# SteppyMk2_10x10.net
KiCad netlist of a schematic drawn in EAGLE
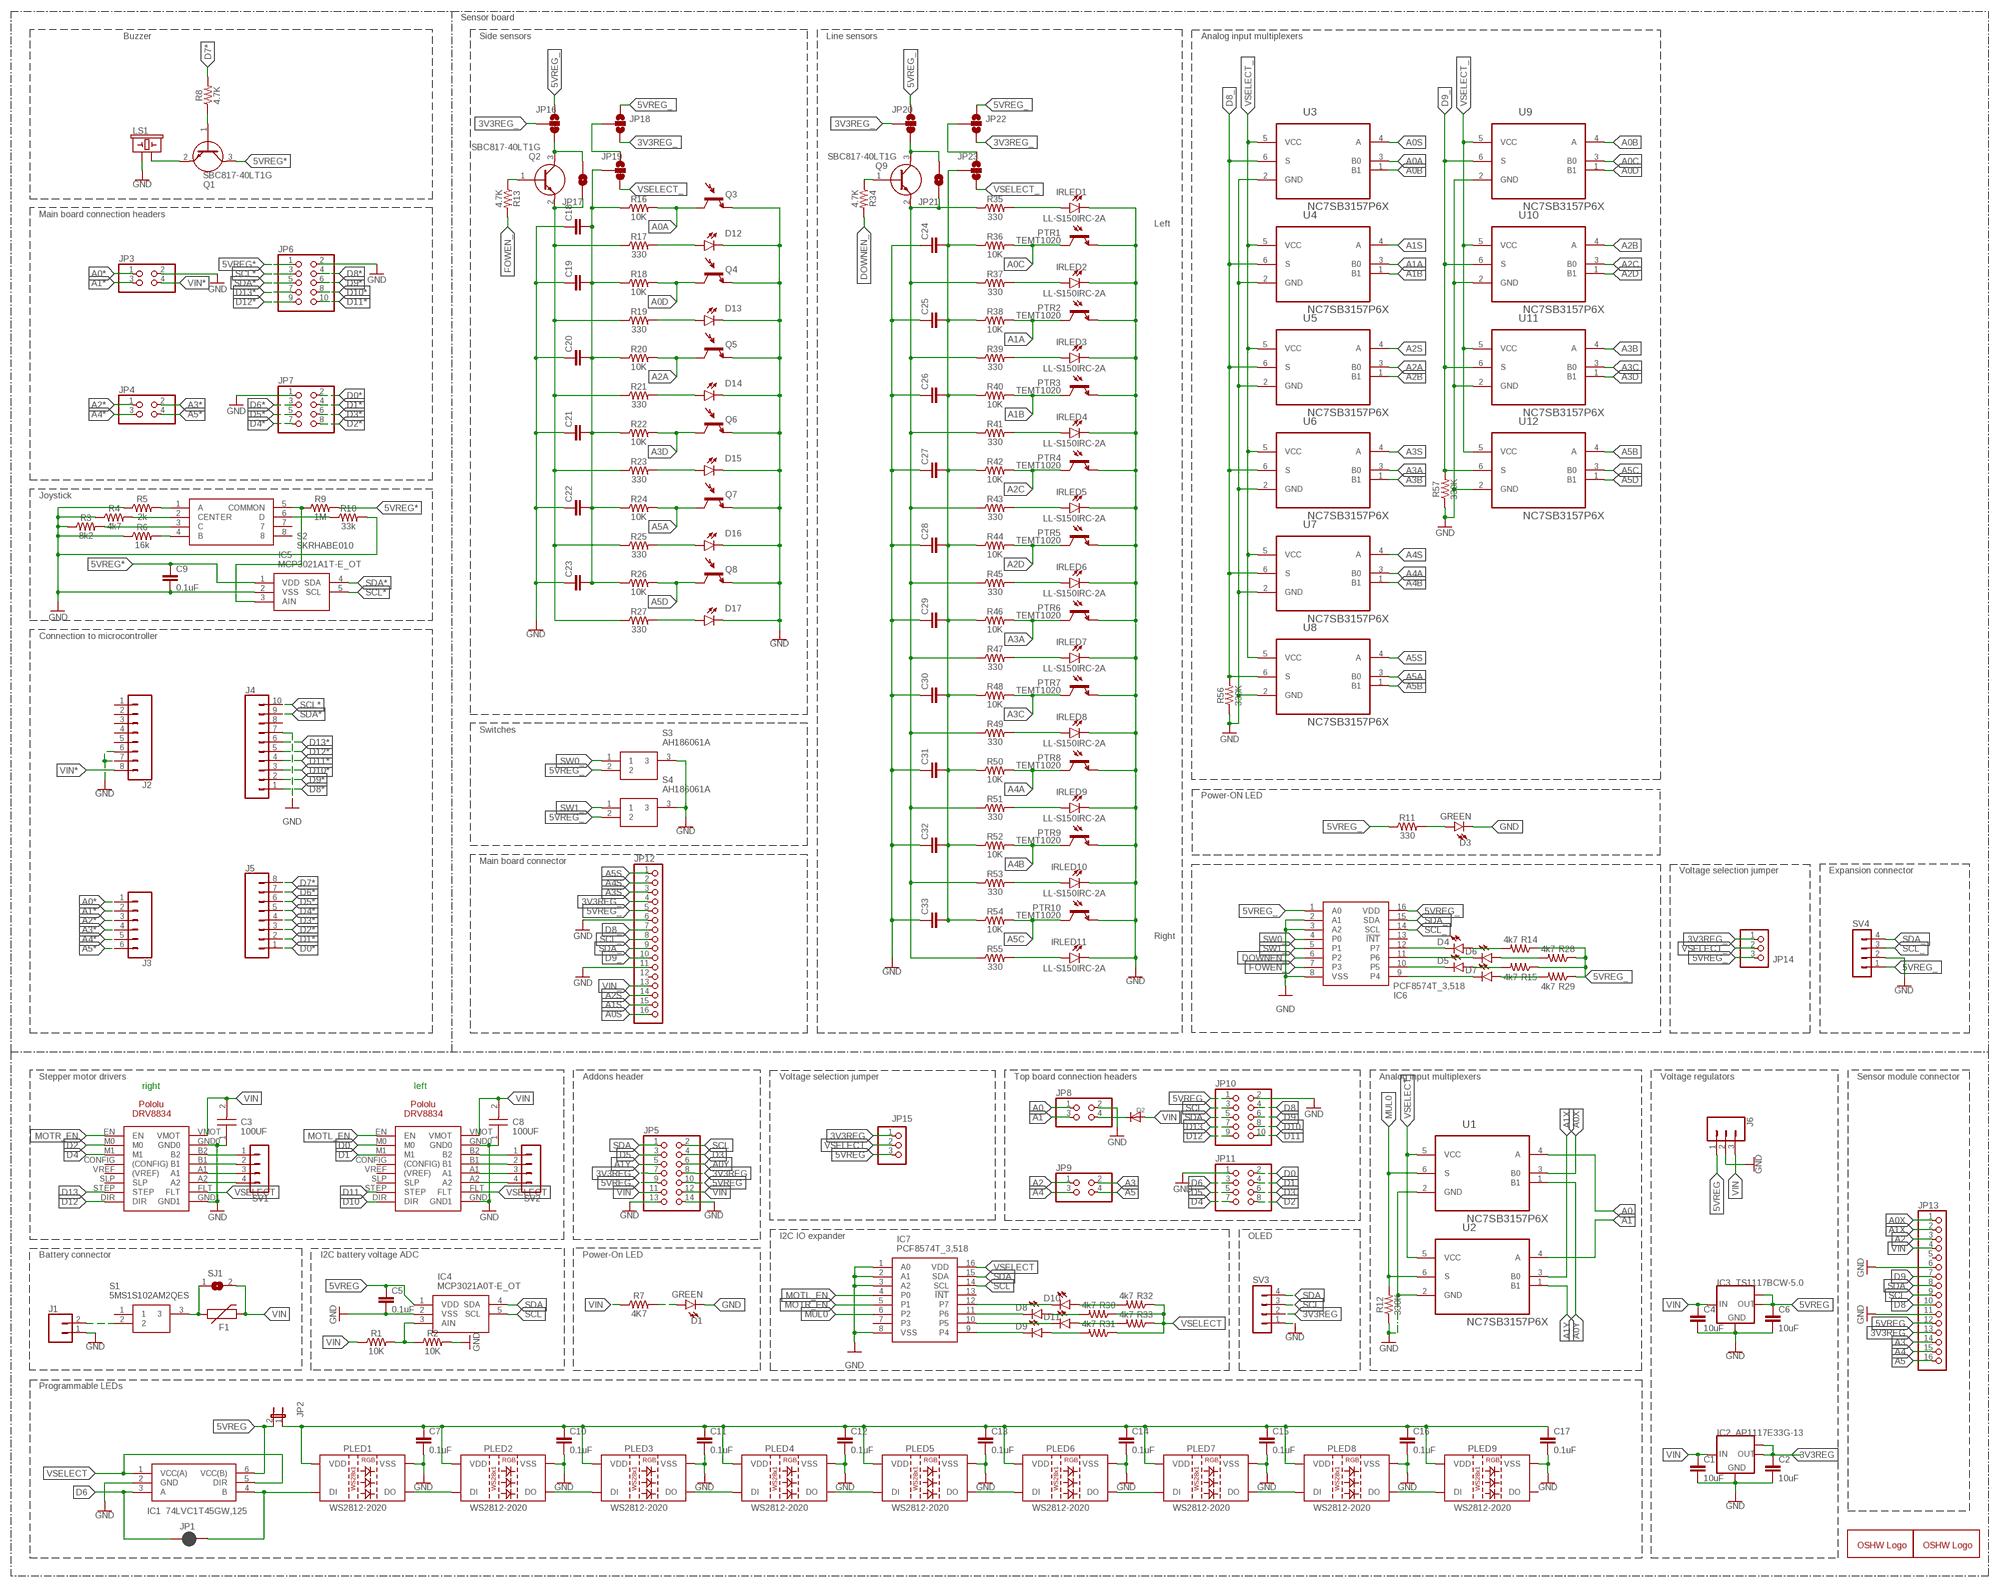
[diagram p0: schematic, sheet 1]

(export (version "E")
  (design (tool "Eeschema 10.0.6"))
  (components
    (comp (ref "C1")
      (value "10uF")
      (footprint "eagle-import:0805")
      (libsource (lib "eagle-import") (part "10UF-0805-10V-10%"))
    )
    (comp (ref "C2")
      (value "10uF")
      (footprint "eagle-import:0805")
      (libsource (lib "eagle-import") (part "10UF-0805-10V-10%"))
    )
    (comp (ref "C3")
      (value "100UF")
      (footprint "eagle-import:CAPM7058X610N")
      (fields
        (field (name "MANUFACTURER_PART_NUMBER") "EEEFK1C101P")
        (field (name "RS_PART_NUMBER") "5370433P")
      )
      (libsource (lib "eagle-import") (part "EEEFK1C101P"))
    )
    (comp (ref "C4")
      (value "10uF")
      (footprint "eagle-import:0805")
      (libsource (lib "eagle-import") (part "10UF-0805-10V-10%"))
    )
    (comp (ref "C5")
      (value "0.1uF")
      (footprint "eagle-import:0603")
      (libsource (lib "eagle-import") (part "0.1UF-0603-25V-5%"))
    )
    (comp (ref "C6")
      (value "10uF")
      (footprint "eagle-import:0805")
      (libsource (lib "eagle-import") (part "10UF-0805-10V-10%"))
    )
    (comp (ref "C7")
      (value "0.1uF")
      (footprint "eagle-import:C0805")
      (libsource (lib "eagle-import") (part "C-EUC0805"))
    )
    (comp (ref "C8")
      (value "100UF")
      (footprint "eagle-import:CAPM7058X610N")
      (fields
        (field (name "MANUFACTURER_PART_NUMBER") "EEEFK1C101P")
        (field (name "RS_PART_NUMBER") "5370433P")
      )
      (libsource (lib "eagle-import") (part "EEEFK1C101P"))
    )
    (comp (ref "C9")
      (value "0.1uF")
      (footprint "eagle-import:C0805")
      (libsource (lib "eagle-import") (part "C-EUC0805"))
    )
    (comp (ref "C10")
      (value "0.1uF")
      (footprint "eagle-import:C0805")
      (libsource (lib "eagle-import") (part "C-EUC0805"))
    )
    (comp (ref "C11")
      (value "0.1uF")
      (footprint "eagle-import:C0805")
      (libsource (lib "eagle-import") (part "C-EUC0805"))
    )
    (comp (ref "C12")
      (value "0.1uF")
      (footprint "eagle-import:C0805")
      (libsource (lib "eagle-import") (part "C-EUC0805"))
    )
    (comp (ref "C13")
      (value "0.1uF")
      (footprint "eagle-import:C0805")
      (libsource (lib "eagle-import") (part "C-EUC0805"))
    )
    (comp (ref "C14")
      (value "0.1uF")
      (footprint "eagle-import:C0805")
      (libsource (lib "eagle-import") (part "C-EUC0805"))
    )
    (comp (ref "C15")
      (value "0.1uF")
      (footprint "eagle-import:C0805")
      (libsource (lib "eagle-import") (part "C-EUC0805"))
    )
    (comp (ref "C16")
      (value "0.1uF")
      (footprint "eagle-import:C0805")
      (libsource (lib "eagle-import") (part "C-EUC0805"))
    )
    (comp (ref "C17")
      (value "0.1uF")
      (footprint "eagle-import:C0805")
      (libsource (lib "eagle-import") (part "C-EUC0805"))
    )
    (comp (ref "C18")
      (value "C-EUC0805")
      (footprint "eagle-import:C0805")
      (libsource (lib "eagle-import") (part "C-EUC0805"))
    )
    (comp (ref "C19")
      (value "C-EUC0805")
      (footprint "eagle-import:C0805")
      (libsource (lib "eagle-import") (part "C-EUC0805"))
    )
    (comp (ref "C20")
      (value "C-EUC0805")
      (footprint "eagle-import:C0805")
      (libsource (lib "eagle-import") (part "C-EUC0805"))
    )
    (comp (ref "C21")
      (value "C-EUC0805")
      (footprint "eagle-import:C0805")
      (libsource (lib "eagle-import") (part "C-EUC0805"))
    )
    (comp (ref "C22")
      (value "C-EUC0805")
      (footprint "eagle-import:C0805")
      (libsource (lib "eagle-import") (part "C-EUC0805"))
    )
    (comp (ref "C23")
      (value "C-EUC0805")
      (footprint "eagle-import:C0805")
      (libsource (lib "eagle-import") (part "C-EUC0805"))
    )
    (comp (ref "C24")
      (value "C-EUC0805")
      (footprint "eagle-import:C0805")
      (libsource (lib "eagle-import") (part "C-EUC0805"))
    )
    (comp (ref "C25")
      (value "C-EUC0805")
      (footprint "eagle-import:C0805")
      (libsource (lib "eagle-import") (part "C-EUC0805"))
    )
    (comp (ref "C26")
      (value "C-EUC0805")
      (footprint "eagle-import:C0805")
      (libsource (lib "eagle-import") (part "C-EUC0805"))
    )
    (comp (ref "C27")
      (value "C-EUC0805")
      (footprint "eagle-import:C0805")
      (libsource (lib "eagle-import") (part "C-EUC0805"))
    )
    (comp (ref "C28")
      (value "C-EUC0805")
      (footprint "eagle-import:C0805")
      (libsource (lib "eagle-import") (part "C-EUC0805"))
    )
    (comp (ref "C29")
      (value "C-EUC0805")
      (footprint "eagle-import:C0805")
      (libsource (lib "eagle-import") (part "C-EUC0805"))
    )
    (comp (ref "C30")
      (value "C-EUC0805")
      (footprint "eagle-import:C0805")
      (libsource (lib "eagle-import") (part "C-EUC0805"))
    )
    (comp (ref "C31")
      (value "C-EUC0805")
      (footprint "eagle-import:C0805")
      (libsource (lib "eagle-import") (part "C-EUC0805"))
    )
    (comp (ref "C32")
      (value "C-EUC0805")
      (footprint "eagle-import:C0805")
      (libsource (lib "eagle-import") (part "C-EUC0805"))
    )
    (comp (ref "C33")
      (value "C-EUC0805")
      (footprint "eagle-import:C0805")
      (libsource (lib "eagle-import") (part "C-EUC0805"))
    )
    (comp (ref "D1")
      (value "GREEN")
      (footprint "eagle-import:LED-1206")
      (libsource (lib "eagle-import") (part "LED-GREEN1206"))
    )
    (comp (ref "D2")
      (value "DIODESMA")
      (footprint "eagle-import:SMADIODE")
      (libsource (lib "eagle-import") (part "DIODESMA"))
    )
    (comp (ref "D3")
      (value "GREEN")
      (footprint "eagle-import:LED-1206")
      (libsource (lib "eagle-import") (part "LED-GREEN1206"))
    )
    (comp (ref "D4")
      (value "GREEN")
      (footprint "eagle-import:LED-1206")
      (libsource (lib "eagle-import") (part "LED-GREEN1206"))
    )
    (comp (ref "D5")
      (value "GREEN")
      (footprint "eagle-import:LED-1206")
      (libsource (lib "eagle-import") (part "LED-GREEN1206"))
    )
    (comp (ref "D6")
      (value "GREEN")
      (footprint "eagle-import:LED-1206")
      (libsource (lib "eagle-import") (part "LED-GREEN1206"))
    )
    (comp (ref "D7")
      (value "GREEN")
      (footprint "eagle-import:LED-1206")
      (libsource (lib "eagle-import") (part "LED-GREEN1206"))
    )
    (comp (ref "D8")
      (value "GREEN")
      (footprint "eagle-import:LED-1206")
      (libsource (lib "eagle-import") (part "LED-GREEN1206"))
    )
    (comp (ref "D9")
      (value "GREEN")
      (footprint "eagle-import:LED-1206")
      (libsource (lib "eagle-import") (part "LED-GREEN1206"))
    )
    (comp (ref "D10")
      (value "GREEN")
      (footprint "eagle-import:LED-1206")
      (libsource (lib "eagle-import") (part "LED-GREEN1206"))
    )
    (comp (ref "D11")
      (value "GREEN")
      (footprint "eagle-import:LED-1206")
      (libsource (lib "eagle-import") (part "LED-GREEN1206"))
    )
    (comp (ref "D12")
      (value "LED-IRSIDE_EMITTER")
      (footprint "eagle-import:LTE-302")
      (libsource (lib "eagle-import") (part "LED-IRSIDE_EMITTER"))
    )
    (comp (ref "D13")
      (value "LED-IRSIDE_EMITTER")
      (footprint "eagle-import:LTE-302")
      (libsource (lib "eagle-import") (part "LED-IRSIDE_EMITTER"))
    )
    (comp (ref "D14")
      (value "LED-IRSIDE_EMITTER")
      (footprint "eagle-import:LTE-302")
      (libsource (lib "eagle-import") (part "LED-IRSIDE_EMITTER"))
    )
    (comp (ref "D15")
      (value "LED-IRSIDE_EMITTER")
      (footprint "eagle-import:LTE-302")
      (libsource (lib "eagle-import") (part "LED-IRSIDE_EMITTER"))
    )
    (comp (ref "D16")
      (value "LED-IRSIDE_EMITTER")
      (footprint "eagle-import:LTE-302")
      (libsource (lib "eagle-import") (part "LED-IRSIDE_EMITTER"))
    )
    (comp (ref "D17")
      (value "LED-IRSIDE_EMITTER")
      (footprint "eagle-import:LTE-302")
      (libsource (lib "eagle-import") (part "LED-IRSIDE_EMITTER"))
    )
    (comp (ref "DRV1")
      (value "POLOLU-DRV8825")
      (footprint "eagle-import:POLOLU-DRV8825")
      (libsource (lib "eagle-import") (part "POLOLU-DRV8825"))
    )
    (comp (ref "DRV2")
      (value "POLOLU-DRV8825")
      (footprint "eagle-import:POLOLU-DRV8825")
      (libsource (lib "eagle-import") (part "POLOLU-DRV8825"))
    )
    (comp (ref "F1")
      (value "PPTC_PTH")
      (footprint "eagle-import:PTH")
      (libsource (lib "eagle-import") (part "PPTC_PTH"))
    )
    (comp (ref "GOLD_ORB_SM1")
      (value "OSHWLOGOLOGO8MM")
      (footprint "eagle-import:OSHW_8MM")
      (libsource (lib "eagle-import") (part "OSHWLOGOLOGO8MM"))
    )
    (comp (ref "GOLD_ORB_SM2")
      (value "OSHWLOGOLOGO5MM")
      (footprint "eagle-import:OSHW_5MM")
      (libsource (lib "eagle-import") (part "OSHWLOGOLOGO5MM"))
    )
    (comp (ref "IC1")
      (value "74LVC1T45GW,125")
      (footprint "eagle-import:SOT65P210X110-6N")
      (fields
        (field (name "MOUSER_PART_NUMBER") "771-74LVC1T45GW125")
        (field (name "RS_PART_NUMBER") "8168791P")
      )
      (libsource (lib "eagle-import") (part "74LVC1T45GW,125"))
    )
    (comp (ref "IC2")
      (value "AP1117E33G-13")
      (footprint "eagle-import:SOT223")
      (libsource (lib "eagle-import") (part "LM1117IMPX-3.3"))
    )
    (comp (ref "IC3")
      (value "TS1117BCW-5.0")
      (footprint "eagle-import:SOT223")
      (libsource (lib "eagle-import") (part "LM1117IMPX-5.0"))
    )
    (comp (ref "IC4")
      (value "MCP3021A0T-E_OT")
      (footprint "eagle-import:SOT95P280X145-5N")
      (fields
        (field (name "MANUFACTURER_PART_NUMBER") "MCP3021A0T-E/OT")
        (field (name "MOUSER_PART_NUMBER") "579-MCP3021A0T-E/OT")
      )
      (libsource (lib "eagle-import") (part "MCP3021A0T-E_OT"))
    )
    (comp (ref "IC5")
      (value "MCP3021A1T-E_OT")
      (footprint "eagle-import:SOT95P280X145-5N")
      (fields
        (field (name "MANUFACTURER_PART_NUMBER") "MCP3021A0T-E/OT")
        (field (name "MOUSER_PART_NUMBER") "579-MCP3021A0T-E/OT")
      )
      (libsource (lib "eagle-import") (part "MCP3021A0T-E_OT"))
    )
    (comp (ref "IC6")
      (value "PCF8574T_3,518")
      (footprint "eagle-import:SOIC127P1032X265-16N")
      (fields
        (field (name "MANUFACTURER_PART_NUMBER") "PCF8574T/3,518")
        (field (name "MOUSER_PART_NUMBER") "771-PCF8574TD-T")
      )
      (libsource (lib "eagle-import") (part "PCF8574T_3,518"))
    )
    (comp (ref "IC7")
      (value "PCF8574T_3,518")
      (footprint "eagle-import:SOIC127P1032X265-16N")
      (fields
        (field (name "MANUFACTURER_PART_NUMBER") "PCF8574T/3,518")
        (field (name "MOUSER_PART_NUMBER") "771-PCF8574TD-T")
      )
      (libsource (lib "eagle-import") (part "PCF8574T_3,518"))
    )
    (comp (ref "IRLED1")
      (value "LL-S150IRC-2A")
      (footprint "eagle-import:LEDC3215X130N")
      (fields
        (field (name "MANUFACTURER_PART_NUMBER") "PT15-21C/TR8")
        (field (name "MOUSER_PART_NUMBER") "638-PT1521CTR8")
      )
      (libsource (lib "eagle-import") (part "PT15-21C_TR8"))
    )
    (comp (ref "IRLED2")
      (value "LL-S150IRC-2A")
      (footprint "eagle-import:LEDC3215X130N")
      (fields
        (field (name "MANUFACTURER_PART_NUMBER") "PT15-21C/TR8")
        (field (name "MOUSER_PART_NUMBER") "638-PT1521CTR8")
      )
      (libsource (lib "eagle-import") (part "PT15-21C_TR8"))
    )
    (comp (ref "IRLED3")
      (value "LL-S150IRC-2A")
      (footprint "eagle-import:LEDC3215X130N")
      (fields
        (field (name "MANUFACTURER_PART_NUMBER") "PT15-21C/TR8")
        (field (name "MOUSER_PART_NUMBER") "638-PT1521CTR8")
      )
      (libsource (lib "eagle-import") (part "PT15-21C_TR8"))
    )
    (comp (ref "IRLED4")
      (value "LL-S150IRC-2A")
      (footprint "eagle-import:LEDC3215X130N")
      (fields
        (field (name "MANUFACTURER_PART_NUMBER") "PT15-21C/TR8")
        (field (name "MOUSER_PART_NUMBER") "638-PT1521CTR8")
      )
      (libsource (lib "eagle-import") (part "PT15-21C_TR8"))
    )
    (comp (ref "IRLED5")
      (value "LL-S150IRC-2A")
      (footprint "eagle-import:LEDC3215X130N")
      (fields
        (field (name "MANUFACTURER_PART_NUMBER") "PT15-21C/TR8")
        (field (name "MOUSER_PART_NUMBER") "638-PT1521CTR8")
      )
      (libsource (lib "eagle-import") (part "PT15-21C_TR8"))
    )
    (comp (ref "IRLED6")
      (value "LL-S150IRC-2A")
      (footprint "eagle-import:LEDC3215X130N")
      (fields
        (field (name "MANUFACTURER_PART_NUMBER") "PT15-21C/TR8")
        (field (name "MOUSER_PART_NUMBER") "638-PT1521CTR8")
      )
      (libsource (lib "eagle-import") (part "PT15-21C_TR8"))
    )
    (comp (ref "IRLED7")
      (value "LL-S150IRC-2A")
      (footprint "eagle-import:LEDC3215X130N")
      (fields
        (field (name "MANUFACTURER_PART_NUMBER") "PT15-21C/TR8")
        (field (name "MOUSER_PART_NUMBER") "638-PT1521CTR8")
      )
      (libsource (lib "eagle-import") (part "PT15-21C_TR8"))
    )
    (comp (ref "IRLED8")
      (value "LL-S150IRC-2A")
      (footprint "eagle-import:LEDC3215X130N")
      (fields
        (field (name "MANUFACTURER_PART_NUMBER") "PT15-21C/TR8")
        (field (name "MOUSER_PART_NUMBER") "638-PT1521CTR8")
      )
      (libsource (lib "eagle-import") (part "PT15-21C_TR8"))
    )
    (comp (ref "IRLED9")
      (value "LL-S150IRC-2A")
      (footprint "eagle-import:LEDC3215X130N")
      (fields
        (field (name "MANUFACTURER_PART_NUMBER") "PT15-21C/TR8")
        (field (name "MOUSER_PART_NUMBER") "638-PT1521CTR8")
      )
      (libsource (lib "eagle-import") (part "PT15-21C_TR8"))
    )
    (comp (ref "IRLED10")
      (value "LL-S150IRC-2A")
      (footprint "eagle-import:LEDC3215X130N")
      (fields
        (field (name "MANUFACTURER_PART_NUMBER") "PT15-21C/TR8")
        (field (name "MOUSER_PART_NUMBER") "638-PT1521CTR8")
      )
      (libsource (lib "eagle-import") (part "PT15-21C_TR8"))
    )
    (comp (ref "IRLED11")
      (value "LL-S150IRC-2A")
      (footprint "eagle-import:LEDC3215X130N")
      (fields
        (field (name "MANUFACTURER_PART_NUMBER") "PT15-21C/TR8")
        (field (name "MOUSER_PART_NUMBER") "638-PT1521CTR8")
      )
      (libsource (lib "eagle-import") (part "PT15-21C_TR8"))
    )
    (comp (ref "J1")
      (value "CONN_02")
      (footprint "eagle-import:1X02")
      (libsource (lib "eagle-import") (part "CONN_02"))
    )
    (comp (ref "J2")
      (value "CONN_08\"")
      (footprint "eagle-import:1X08")
      (libsource (lib "eagle-import") (part "CONN_08{dblquote}"))
    )
    (comp (ref "J3")
      (value "CONN_06SILK_FEMALE_PTH")
      (footprint "eagle-import:1X06")
      (libsource (lib "eagle-import") (part "CONN_06SILK_FEMALE_PTH"))
    )
    (comp (ref "J4")
      (value "CONN_10\"")
      (footprint "eagle-import:1X10")
      (libsource (lib "eagle-import") (part "CONN_10{dblquote}"))
    )
    (comp (ref "J5")
      (value "CONN_08\"")
      (footprint "eagle-import:1X08")
      (libsource (lib "eagle-import") (part "CONN_08{dblquote}"))
    )
    (comp (ref "J6")
      (value "455-1750-1-ND")
      (footprint "eagle-import:1X03")
      (libsource (lib "eagle-import") (part "CONN_03"))
    )
    (comp (ref "JP1")
      (value "JUMPER-SMT_2_NC_PASTE_SILK")
      (footprint "eagle-import:SMT-JUMPER_2_NC_PASTE_SILK")
      (libsource (lib "eagle-import") (part "JUMPER-SMT_2_NC_PASTE_SILK"))
    )
    (comp (ref "JP2")
      (value "JP1E")
      (footprint "eagle-import:JP1")
      (libsource (lib "eagle-import") (part "JP1E"))
    )
    (comp (ref "JP3")
      (value "PINHD-2X2")
      (footprint "eagle-import:2X02")
      (libsource (lib "eagle-import") (part "PINHD-2X2"))
    )
    (comp (ref "JP4")
      (value "PINHD-2X2")
      (footprint "eagle-import:2X02")
      (libsource (lib "eagle-import") (part "PINHD-2X2"))
    )
    (comp (ref "JP5")
      (value "PINHD-2X7")
      (footprint "eagle-import:2X07")
      (libsource (lib "eagle-import") (part "PINHD-2X7"))
    )
    (comp (ref "JP6")
      (value "PINHD-2X5")
      (footprint "eagle-import:2X05")
      (libsource (lib "eagle-import") (part "PINHD-2X5"))
    )
    (comp (ref "JP7")
      (value "PINHD-2X4")
      (footprint "eagle-import:2X04")
      (libsource (lib "eagle-import") (part "PINHD-2X4"))
    )
    (comp (ref "JP8")
      (value "PINHD-2X2")
      (footprint "eagle-import:2X02")
      (libsource (lib "eagle-import") (part "PINHD-2X2"))
    )
    (comp (ref "JP9")
      (value "PINHD-2X2")
      (footprint "eagle-import:2X02")
      (libsource (lib "eagle-import") (part "PINHD-2X2"))
    )
    (comp (ref "JP10")
      (value "PINHD-2X5")
      (footprint "eagle-import:2X05")
      (libsource (lib "eagle-import") (part "PINHD-2X5"))
    )
    (comp (ref "JP11")
      (value "PINHD-2X4")
      (footprint "eagle-import:2X04")
      (libsource (lib "eagle-import") (part "PINHD-2X4"))
    )
    (comp (ref "JP12")
      (value "PINHD-1X16/90")
      (footprint "eagle-import:1X16_90")
      (libsource (lib "eagle-import") (part "PINHD-1X16/90"))
    )
    (comp (ref "JP13")
      (value "PINHD-1X16")
      (footprint "eagle-import:1X16")
      (libsource (lib "eagle-import") (part "PINHD-1X16"))
    )
    (comp (ref "JP14")
      (value "PINHD-1X3")
      (footprint "eagle-import:1X03")
      (libsource (lib "eagle-import") (part "PINHD-1X3"))
    )
    (comp (ref "JP15")
      (value "PINHD-1X3")
      (footprint "eagle-import:1X03")
      (libsource (lib "eagle-import") (part "PINHD-1X3"))
    )
    (comp (ref "JP16")
      (value "JUMPER-SMT_3_1-NC_TRACE_NO-SILK")
      (footprint "eagle-import:SMT-JUMPER_3_1-NC_TRACE_NO-SILK")
      (libsource (lib "eagle-import") (part "JUMPER-SMT_3_1-NC_TRACE_NO-SILK"))
    )
    (comp (ref "JP17")
      (value "JUMPER-SMT_2_NO_NO-SILK")
      (footprint "eagle-import:SMT-JUMPER_2_NO_NO-SILK")
      (libsource (lib "eagle-import") (part "JUMPER-SMT_2_NO_NO-SILK"))
    )
    (comp (ref "JP18")
      (value "JUMPER-SMT_3_NO_NO_SILK")
      (footprint "eagle-import:SMT-JUMPER_3_0-NO_TRACE_NO-SILK")
      (libsource (lib "eagle-import") (part "JUMPER-SMT_3_NO_NO_SILK"))
    )
    (comp (ref "JP19")
      (value "JUMPER-SMT_3_1-NC_TRACE_NO-SILK")
      (footprint "eagle-import:SMT-JUMPER_3_1-NC_TRACE_NO-SILK")
      (libsource (lib "eagle-import") (part "JUMPER-SMT_3_1-NC_TRACE_NO-SILK"))
    )
    (comp (ref "JP20")
      (value "JUMPER-SMT_3_1-NC_TRACE_NO-SILK")
      (footprint "eagle-import:SMT-JUMPER_3_1-NC_TRACE_NO-SILK")
      (libsource (lib "eagle-import") (part "JUMPER-SMT_3_1-NC_TRACE_NO-SILK"))
    )
    (comp (ref "JP21")
      (value "JUMPER-SMT_2_NO_NO-SILK")
      (footprint "eagle-import:SMT-JUMPER_2_NO_NO-SILK")
      (libsource (lib "eagle-import") (part "JUMPER-SMT_2_NO_NO-SILK"))
    )
    (comp (ref "JP22")
      (value "JUMPER-SMT_3_NO_NO_SILK")
      (footprint "eagle-import:SMT-JUMPER_3_0-NO_TRACE_NO-SILK")
      (libsource (lib "eagle-import") (part "JUMPER-SMT_3_NO_NO_SILK"))
    )
    (comp (ref "JP23")
      (value "JUMPER-SMT_3_1-NC_TRACE_NO-SILK")
      (footprint "eagle-import:SMT-JUMPER_3_1-NC_TRACE_NO-SILK")
      (libsource (lib "eagle-import") (part "JUMPER-SMT_3_1-NC_TRACE_NO-SILK"))
    )
    (comp (ref "LS1")
      (value "BUZZER-PTH_NO_SILK")
      (footprint "eagle-import:BUZZER-12MM-NS")
      (libsource (lib "eagle-import") (part "BUZZER-PTH_NO_SILK"))
    )
    (comp (ref "PLED1")
      (value "WS2812-2020")
      (footprint "eagle-import:WS2812-2020")
      (libsource (lib "eagle-import") (part "WS2812-2020"))
    )
    (comp (ref "PLED2")
      (value "WS2812-2020")
      (footprint "eagle-import:WS2812-2020")
      (libsource (lib "eagle-import") (part "WS2812-2020"))
    )
    (comp (ref "PLED3")
      (value "WS2812-2020")
      (footprint "eagle-import:WS2812-2020")
      (libsource (lib "eagle-import") (part "WS2812-2020"))
    )
    (comp (ref "PLED4")
      (value "WS2812-2020")
      (footprint "eagle-import:WS2812-2020")
      (libsource (lib "eagle-import") (part "WS2812-2020"))
    )
    (comp (ref "PLED5")
      (value "WS2812-2020")
      (footprint "eagle-import:WS2812-2020")
      (libsource (lib "eagle-import") (part "WS2812-2020"))
    )
    (comp (ref "PLED6")
      (value "WS2812-2020")
      (footprint "eagle-import:WS2812-2020")
      (libsource (lib "eagle-import") (part "WS2812-2020"))
    )
    (comp (ref "PLED7")
      (value "WS2812-2020")
      (footprint "eagle-import:WS2812-2020")
      (libsource (lib "eagle-import") (part "WS2812-2020"))
    )
    (comp (ref "PLED8")
      (value "WS2812-2020")
      (footprint "eagle-import:WS2812-2020")
      (libsource (lib "eagle-import") (part "WS2812-2020"))
    )
    (comp (ref "PLED9")
      (value "WS2812-2020")
      (footprint "eagle-import:WS2812-2020")
      (libsource (lib "eagle-import") (part "WS2812-2020"))
    )
    (comp (ref "PTR1")
      (value "TEMT1020")
      (footprint "eagle-import:TEMT1020")
      (fields
        (field (name "MANUFACTURER_PART_NUMBER") "TEMD1020")
        (field (name "MOUSER_PART_NUMBER") "782-TEMD1020")
        (field (name "RS_PART_NUMBER") "1808105P")
      )
      (libsource (lib "eagle-import") (part "TEMT1020"))
    )
    (comp (ref "PTR2")
      (value "TEMT1020")
      (footprint "eagle-import:TEMT1020")
      (fields
        (field (name "MANUFACTURER_PART_NUMBER") "TEMD1020")
        (field (name "MOUSER_PART_NUMBER") "782-TEMD1020")
        (field (name "RS_PART_NUMBER") "1808105P")
      )
      (libsource (lib "eagle-import") (part "TEMT1020"))
    )
    (comp (ref "PTR3")
      (value "TEMT1020")
      (footprint "eagle-import:TEMT1020")
      (fields
        (field (name "MANUFACTURER_PART_NUMBER") "TEMD1020")
        (field (name "MOUSER_PART_NUMBER") "782-TEMD1020")
        (field (name "RS_PART_NUMBER") "1808105P")
      )
      (libsource (lib "eagle-import") (part "TEMT1020"))
    )
    (comp (ref "PTR4")
      (value "TEMT1020")
      (footprint "eagle-import:TEMT1020")
      (fields
        (field (name "MANUFACTURER_PART_NUMBER") "TEMD1020")
        (field (name "MOUSER_PART_NUMBER") "782-TEMD1020")
        (field (name "RS_PART_NUMBER") "1808105P")
      )
      (libsource (lib "eagle-import") (part "TEMT1020"))
    )
    (comp (ref "PTR5")
      (value "TEMT1020")
      (footprint "eagle-import:TEMT1020")
      (fields
        (field (name "MANUFACTURER_PART_NUMBER") "TEMD1020")
        (field (name "MOUSER_PART_NUMBER") "782-TEMD1020")
        (field (name "RS_PART_NUMBER") "1808105P")
      )
      (libsource (lib "eagle-import") (part "TEMT1020"))
    )
    (comp (ref "PTR6")
      (value "TEMT1020")
      (footprint "eagle-import:TEMT1020")
      (fields
        (field (name "MANUFACTURER_PART_NUMBER") "TEMD1020")
        (field (name "MOUSER_PART_NUMBER") "782-TEMD1020")
        (field (name "RS_PART_NUMBER") "1808105P")
      )
      (libsource (lib "eagle-import") (part "TEMT1020"))
    )
    (comp (ref "PTR7")
      (value "TEMT1020")
      (footprint "eagle-import:TEMT1020")
      (fields
        (field (name "MANUFACTURER_PART_NUMBER") "TEMD1020")
        (field (name "MOUSER_PART_NUMBER") "782-TEMD1020")
        (field (name "RS_PART_NUMBER") "1808105P")
      )
      (libsource (lib "eagle-import") (part "TEMT1020"))
    )
    (comp (ref "PTR8")
      (value "TEMT1020")
      (footprint "eagle-import:TEMT1020")
      (fields
        (field (name "MANUFACTURER_PART_NUMBER") "TEMD1020")
        (field (name "MOUSER_PART_NUMBER") "782-TEMD1020")
        (field (name "RS_PART_NUMBER") "1808105P")
      )
      (libsource (lib "eagle-import") (part "TEMT1020"))
    )
    (comp (ref "PTR9")
      (value "TEMT1020")
      (footprint "eagle-import:TEMT1020")
      (fields
        (field (name "MANUFACTURER_PART_NUMBER") "TEMD1020")
        (field (name "MOUSER_PART_NUMBER") "782-TEMD1020")
        (field (name "RS_PART_NUMBER") "1808105P")
      )
      (libsource (lib "eagle-import") (part "TEMT1020"))
    )
    (comp (ref "PTR10")
      (value "TEMT1020")
      (footprint "eagle-import:TEMT1020")
      (fields
        (field (name "MANUFACTURER_PART_NUMBER") "TEMD1020")
        (field (name "MOUSER_PART_NUMBER") "782-TEMD1020")
        (field (name "RS_PART_NUMBER") "1808105P")
      )
      (libsource (lib "eagle-import") (part "TEMT1020"))
    )
    (comp (ref "Q1")
      (value "SBC817-40LT1G")
      (footprint "eagle-import:SOT96P237X111-3N")
      (fields
        (field (name "MOUSER_PART_NUMBER") "863-SBC817-40LT1G")
        (field (name "RS_PART_NUMBER") "1631159")
      )
      (libsource (lib "eagle-import") (part "SBC817-40LT1G"))
    )
    (comp (ref "Q2")
      (value "SBC817-40LT1G")
      (footprint "eagle-import:SOT96P237X111-3N")
      (fields
        (field (name "MOUSER_PART_NUMBER") "863-SBC817-40LT1G")
        (field (name "RS_PART_NUMBER") "1631159")
      )
      (libsource (lib "eagle-import") (part "SBC817-40LT1G"))
    )
    (comp (ref "Q3")
      (value "LTR-301")
      (footprint "eagle-import:LTR-301")
      (libsource (lib "eagle-import") (part "LTR-301"))
    )
    (comp (ref "Q4")
      (value "LTR-301")
      (footprint "eagle-import:LTR-301")
      (libsource (lib "eagle-import") (part "LTR-301"))
    )
    (comp (ref "Q5")
      (value "LTR-301")
      (footprint "eagle-import:LTR-301")
      (libsource (lib "eagle-import") (part "LTR-301"))
    )
    (comp (ref "Q6")
      (value "LTR-301")
      (footprint "eagle-import:LTR-301")
      (libsource (lib "eagle-import") (part "LTR-301"))
    )
    (comp (ref "Q7")
      (value "LTR-301")
      (footprint "eagle-import:LTR-301")
      (libsource (lib "eagle-import") (part "LTR-301"))
    )
    (comp (ref "Q8")
      (value "LTR-301")
      (footprint "eagle-import:LTR-301")
      (libsource (lib "eagle-import") (part "LTR-301"))
    )
    (comp (ref "Q9")
      (value "SBC817-40LT1G")
      (footprint "eagle-import:SOT96P237X111-3N")
      (fields
        (field (name "MOUSER_PART_NUMBER") "863-SBC817-40LT1G")
        (field (name "RS_PART_NUMBER") "1631159")
      )
      (libsource (lib "eagle-import") (part "SBC817-40LT1G"))
    )
    (comp (ref "R1")
      (value "10K")
      (footprint "eagle-import:0805")
      (libsource (lib "eagle-import") (part "RESISTOR0805"))
    )
    (comp (ref "R2")
      (value "10K")
      (footprint "eagle-import:0805")
      (libsource (lib "eagle-import") (part "RESISTOR0805"))
    )
    (comp (ref "R3")
      (value "8k2")
      (footprint "eagle-import:0805")
      (libsource (lib "eagle-import") (part "RESISTOR0805"))
    )
    (comp (ref "R4")
      (value "4k7")
      (footprint "eagle-import:0805")
      (libsource (lib "eagle-import") (part "RESISTOR0805"))
    )
    (comp (ref "R5")
      (value "2k")
      (footprint "eagle-import:0805")
      (libsource (lib "eagle-import") (part "RESISTOR0805"))
    )
    (comp (ref "R6")
      (value "16k")
      (footprint "eagle-import:0805")
      (libsource (lib "eagle-import") (part "RESISTOR0805"))
    )
    (comp (ref "R7")
      (value "4K7")
      (footprint "eagle-import:0805")
      (libsource (lib "eagle-import") (part "RESISTOR0805"))
    )
    (comp (ref "R8")
      (value "4.7K")
      (footprint "eagle-import:0805")
      (libsource (lib "eagle-import") (part "RESISTOR0805"))
    )
    (comp (ref "R9")
      (value "1M")
      (footprint "eagle-import:0805")
      (libsource (lib "eagle-import") (part "RESISTOR0805"))
    )
    (comp (ref "R10")
      (value "33k")
      (footprint "eagle-import:0805")
      (libsource (lib "eagle-import") (part "RESISTOR0805"))
    )
    (comp (ref "R11")
      (value "330")
      (footprint "eagle-import:0805")
      (libsource (lib "eagle-import") (part "RESISTOR0805"))
    )
    (comp (ref "R12")
      (value "330K")
      (footprint "eagle-import:0805")
      (libsource (lib "eagle-import") (part "RESISTOR0805"))
    )
    (comp (ref "R13")
      (value "4.7K")
      (footprint "eagle-import:0805")
      (libsource (lib "eagle-import") (part "RESISTOR0805"))
    )
    (comp (ref "R14")
      (value "4k7")
      (footprint "eagle-import:0805")
      (libsource (lib "eagle-import") (part "RESISTOR0805"))
    )
    (comp (ref "R15")
      (value "4k7")
      (footprint "eagle-import:0805")
      (libsource (lib "eagle-import") (part "RESISTOR0805"))
    )
    (comp (ref "R16")
      (value "10K")
      (footprint "eagle-import:0805")
      (libsource (lib "eagle-import") (part "RESISTOR0805"))
    )
    (comp (ref "R17")
      (value "330")
      (footprint "eagle-import:0805")
      (libsource (lib "eagle-import") (part "RESISTOR0805"))
    )
    (comp (ref "R18")
      (value "10K")
      (footprint "eagle-import:0805")
      (libsource (lib "eagle-import") (part "RESISTOR0805"))
    )
    (comp (ref "R19")
      (value "330")
      (footprint "eagle-import:0805")
      (libsource (lib "eagle-import") (part "RESISTOR0805"))
    )
    (comp (ref "R20")
      (value "10K")
      (footprint "eagle-import:0805")
      (libsource (lib "eagle-import") (part "RESISTOR0805"))
    )
    (comp (ref "R21")
      (value "330")
      (footprint "eagle-import:0805")
      (libsource (lib "eagle-import") (part "RESISTOR0805"))
    )
    (comp (ref "R22")
      (value "10K")
      (footprint "eagle-import:0805")
      (libsource (lib "eagle-import") (part "RESISTOR0805"))
    )
    (comp (ref "R23")
      (value "330")
      (footprint "eagle-import:0805")
      (libsource (lib "eagle-import") (part "RESISTOR0805"))
    )
    (comp (ref "R24")
      (value "10K")
      (footprint "eagle-import:0805")
      (libsource (lib "eagle-import") (part "RESISTOR0805"))
    )
    (comp (ref "R25")
      (value "330")
      (footprint "eagle-import:0805")
      (libsource (lib "eagle-import") (part "RESISTOR0805"))
    )
    (comp (ref "R26")
      (value "10K")
      (footprint "eagle-import:0805")
      (libsource (lib "eagle-import") (part "RESISTOR0805"))
    )
    (comp (ref "R27")
      (value "330")
      (footprint "eagle-import:0805")
      (libsource (lib "eagle-import") (part "RESISTOR0805"))
    )
    (comp (ref "R28")
      (value "4k7")
      (footprint "eagle-import:0805")
      (libsource (lib "eagle-import") (part "RESISTOR0805"))
    )
    (comp (ref "R29")
      (value "4k7")
      (footprint "eagle-import:0805")
      (libsource (lib "eagle-import") (part "RESISTOR0805"))
    )
    (comp (ref "R30")
      (value "4k7")
      (footprint "eagle-import:0805")
      (libsource (lib "eagle-import") (part "RESISTOR0805"))
    )
    (comp (ref "R31")
      (value "4k7")
      (footprint "eagle-import:0805")
      (libsource (lib "eagle-import") (part "RESISTOR0805"))
    )
    (comp (ref "R32")
      (value "4k7")
      (footprint "eagle-import:0805")
      (libsource (lib "eagle-import") (part "RESISTOR0805"))
    )
    (comp (ref "R33")
      (value "4k7")
      (footprint "eagle-import:0805")
      (libsource (lib "eagle-import") (part "RESISTOR0805"))
    )
    (comp (ref "R34")
      (value "4.7K")
      (footprint "eagle-import:0805")
      (libsource (lib "eagle-import") (part "RESISTOR0805"))
    )
    (comp (ref "R35")
      (value "330")
      (footprint "eagle-import:0805")
      (libsource (lib "eagle-import") (part "RESISTOR0805"))
    )
    (comp (ref "R36")
      (value "10K")
      (footprint "eagle-import:0805")
      (libsource (lib "eagle-import") (part "RESISTOR0805"))
    )
    (comp (ref "R37")
      (value "330")
      (footprint "eagle-import:0805")
      (libsource (lib "eagle-import") (part "RESISTOR0805"))
    )
    (comp (ref "R38")
      (value "10K")
      (footprint "eagle-import:0805")
      (libsource (lib "eagle-import") (part "RESISTOR0805"))
    )
    (comp (ref "R39")
      (value "330")
      (footprint "eagle-import:0805")
      (libsource (lib "eagle-import") (part "RESISTOR0805"))
    )
    (comp (ref "R40")
      (value "10K")
      (footprint "eagle-import:0805")
      (libsource (lib "eagle-import") (part "RESISTOR0805"))
    )
    (comp (ref "R41")
      (value "330")
      (footprint "eagle-import:0805")
      (libsource (lib "eagle-import") (part "RESISTOR0805"))
    )
    (comp (ref "R42")
      (value "10K")
      (footprint "eagle-import:0805")
      (libsource (lib "eagle-import") (part "RESISTOR0805"))
    )
    (comp (ref "R43")
      (value "330")
      (footprint "eagle-import:0805")
      (libsource (lib "eagle-import") (part "RESISTOR0805"))
    )
    (comp (ref "R44")
      (value "10K")
      (footprint "eagle-import:0805")
      (libsource (lib "eagle-import") (part "RESISTOR0805"))
    )
    (comp (ref "R45")
      (value "330")
      (footprint "eagle-import:0805")
      (libsource (lib "eagle-import") (part "RESISTOR0805"))
    )
    (comp (ref "R46")
      (value "10K")
      (footprint "eagle-import:0805")
      (libsource (lib "eagle-import") (part "RESISTOR0805"))
    )
    (comp (ref "R47")
      (value "330")
      (footprint "eagle-import:0805")
      (libsource (lib "eagle-import") (part "RESISTOR0805"))
    )
    (comp (ref "R48")
      (value "10K")
      (footprint "eagle-import:0805")
      (libsource (lib "eagle-import") (part "RESISTOR0805"))
    )
    (comp (ref "R49")
      (value "330")
      (footprint "eagle-import:0805")
      (libsource (lib "eagle-import") (part "RESISTOR0805"))
    )
    (comp (ref "R50")
      (value "10K")
      (footprint "eagle-import:0805")
      (libsource (lib "eagle-import") (part "RESISTOR0805"))
    )
    (comp (ref "R51")
      (value "330")
      (footprint "eagle-import:0805")
      (libsource (lib "eagle-import") (part "RESISTOR0805"))
    )
    (comp (ref "R52")
      (value "10K")
      (footprint "eagle-import:0805")
      (libsource (lib "eagle-import") (part "RESISTOR0805"))
    )
    (comp (ref "R53")
      (value "330")
      (footprint "eagle-import:0805")
      (libsource (lib "eagle-import") (part "RESISTOR0805"))
    )
    (comp (ref "R54")
      (value "10K")
      (footprint "eagle-import:0805")
      (libsource (lib "eagle-import") (part "RESISTOR0805"))
    )
    (comp (ref "R55")
      (value "330")
      (footprint "eagle-import:0805")
      (libsource (lib "eagle-import") (part "RESISTOR0805"))
    )
    (comp (ref "R56")
      (value "330K")
      (footprint "eagle-import:0805")
      (libsource (lib "eagle-import") (part "RESISTOR0805"))
    )
    (comp (ref "R57")
      (value "330K")
      (footprint "eagle-import:0805")
      (libsource (lib "eagle-import") (part "RESISTOR0805"))
    )
    (comp (ref "S1")
      (value "5MS1S102AM2QES")
      (footprint "eagle-import:5MS1S102AM2QES")
      (fields (field (name "RS_PART_NUMBER") "7347292"))
      (libsource (lib "eagle-import") (part "5MS1S102AM2QES"))
    )
    (comp (ref "S2")
      (value "SKRHABE010")
      (footprint "eagle-import:SKRHABE010")
      (fields (field (name "MOUSER_PART_NUMBER") "688-SKRHAB"))
      (libsource (lib "eagle-import") (part "SKRHABE010"))
    )
    (comp (ref "S3")
      (value "AH186061A")
      (footprint "eagle-import:AH186061A")
      (libsource (lib "eagle-import") (part "AH186061A"))
    )
    (comp (ref "S4")
      (value "AH186061A")
      (footprint "eagle-import:AH186061A")
      (libsource (lib "eagle-import") (part "AH186061A"))
    )
    (comp (ref "SJ1")
      (value "SJW")
      (footprint "eagle-import:SJW")
      (libsource (lib "eagle-import") (part "SJW"))
    )
    (comp (ref "SV1")
      (value "MA04-1")
      (footprint "eagle-import:MA04-1")
      (libsource (lib "eagle-import") (part "MA04-1"))
    )
    (comp (ref "SV2")
      (value "MA04-1")
      (footprint "eagle-import:MA04-1")
      (libsource (lib "eagle-import") (part "MA04-1"))
    )
    (comp (ref "SV3")
      (value "MA04-1")
      (footprint "eagle-import:MA04-1")
      (libsource (lib "eagle-import") (part "MA04-1"))
    )
    (comp (ref "SV4")
      (value "MA04-1")
      (footprint "eagle-import:MA04-1")
      (libsource (lib "eagle-import") (part "MA04-1"))
    )
    (comp (ref "U1")
      (value "NC7SB3157P6X")
      (footprint "eagle-import:SOT65P210X110-6N")
      (fields (field (name "MF") "ON Semiconductor"))
      (libsource (lib "eagle-import") (part "NC7SB3157P6X"))
    )
    (comp (ref "U2")
      (value "NC7SB3157P6X")
      (footprint "eagle-import:SOT65P210X110-6N")
      (fields (field (name "MF") "ON Semiconductor"))
      (libsource (lib "eagle-import") (part "NC7SB3157P6X"))
    )
    (comp (ref "U3")
      (value "NC7SB3157P6X")
      (footprint "eagle-import:SOT65P210X110-6N")
      (fields (field (name "MF") "ON Semiconductor"))
      (libsource (lib "eagle-import") (part "NC7SB3157P6X"))
    )
    (comp (ref "U4")
      (value "NC7SB3157P6X")
      (footprint "eagle-import:SOT65P210X110-6N")
      (fields (field (name "MF") "ON Semiconductor"))
      (libsource (lib "eagle-import") (part "NC7SB3157P6X"))
    )
    (comp (ref "U5")
      (value "NC7SB3157P6X")
      (footprint "eagle-import:SOT65P210X110-6N")
      (fields (field (name "MF") "ON Semiconductor"))
      (libsource (lib "eagle-import") (part "NC7SB3157P6X"))
    )
    (comp (ref "U6")
      (value "NC7SB3157P6X")
      (footprint "eagle-import:SOT65P210X110-6N")
      (fields (field (name "MF") "ON Semiconductor"))
      (libsource (lib "eagle-import") (part "NC7SB3157P6X"))
    )
    (comp (ref "U7")
      (value "NC7SB3157P6X")
      (footprint "eagle-import:SOT65P210X110-6N")
      (fields (field (name "MF") "ON Semiconductor"))
      (libsource (lib "eagle-import") (part "NC7SB3157P6X"))
    )
    (comp (ref "U8")
      (value "NC7SB3157P6X")
      (footprint "eagle-import:SOT65P210X110-6N")
      (fields (field (name "MF") "ON Semiconductor"))
      (libsource (lib "eagle-import") (part "NC7SB3157P6X"))
    )
    (comp (ref "U9")
      (value "NC7SB3157P6X")
      (footprint "eagle-import:SOT65P210X110-6N")
      (fields (field (name "MF") "ON Semiconductor"))
      (libsource (lib "eagle-import") (part "NC7SB3157P6X"))
    )
    (comp (ref "U10")
      (value "NC7SB3157P6X")
      (footprint "eagle-import:SOT65P210X110-6N")
      (fields (field (name "MF") "ON Semiconductor"))
      (libsource (lib "eagle-import") (part "NC7SB3157P6X"))
    )
    (comp (ref "U11")
      (value "NC7SB3157P6X")
      (footprint "eagle-import:SOT65P210X110-6N")
      (fields (field (name "MF") "ON Semiconductor"))
      (libsource (lib "eagle-import") (part "NC7SB3157P6X"))
    )
    (comp (ref "U12")
      (value "NC7SB3157P6X")
      (footprint "eagle-import:SOT65P210X110-6N")
      (fields (field (name "MF") "ON Semiconductor"))
      (libsource (lib "eagle-import") (part "NC7SB3157P6X"))
    )
  )
  (nets
    (net (code "1") (name "3V3REG") (class "Default")
      (node (ref "C2") (pin "1") (pinfunction "1_1") (pintype "passive"))
      (node (ref "IC2") (pin "2") (pinfunction "OUT_2") (pintype "passive"))
      (node (ref "IC2") (pin "TAB") (pinfunction "OUT1_TAB") (pintype "passive"))
      (node (ref "JP13") (pin "13") (pinfunction "13_13") (pintype "passive"))
      (node (ref "JP15") (pin "1") (pinfunction "1_1") (pintype "passive"))
      (node (ref "JP5") (pin "7") (pinfunction "7_7") (pintype "passive"))
      (node (ref "JP5") (pin "8") (pinfunction "8_8") (pintype "passive"))
      (node (ref "SV3") (pin "2") (pinfunction "2_2") (pintype "passive"))
    )
    (net (code "2") (name "3V3REG_") (class "Default")
      (node (ref "JP12") (pin "4") (pinfunction "4_4") (pintype "passive"))
      (node (ref "JP14") (pin "1") (pinfunction "1_1") (pintype "passive"))
      (node (ref "JP16") (pin "2") (pinfunction "2_2") (pintype "passive"))
      (node (ref "JP18") (pin "3") (pinfunction "3_3") (pintype "passive"))
      (node (ref "JP20") (pin "2") (pinfunction "2_2") (pintype "passive"))
      (node (ref "JP22") (pin "3") (pinfunction "3_3") (pintype "passive"))
    )
    (net (code "3") (name "5VREG") (class "Default")
      (node (ref "C5") (pin "1") (pinfunction "1_1") (pintype "passive"))
      (node (ref "C6") (pin "1") (pinfunction "1_1") (pintype "passive"))
      (node (ref "IC1") (pin "6") (pinfunction "VCC(B)_6") (pintype "power_in"))
      (node (ref "IC3") (pin "2") (pinfunction "OUT_2") (pintype "passive"))
      (node (ref "IC3") (pin "TAB") (pinfunction "OUT1_TAB") (pintype "passive"))
      (node (ref "IC4") (pin "1") (pinfunction "VDD_1") (pintype "bidirectional"))
      (node (ref "J6") (pin "1") (pinfunction "1_1") (pintype "passive"))
      (node (ref "JP10") (pin "1") (pinfunction "1_1") (pintype "passive"))
      (node (ref "JP13") (pin "12") (pinfunction "12_12") (pintype "passive"))
      (node (ref "JP15") (pin "3") (pinfunction "3_3") (pintype "passive"))
      (node (ref "JP2") (pin "2") (pinfunction "2_2") (pintype "passive"))
      (node (ref "JP5") (pin "10") (pinfunction "10_10") (pintype "passive"))
      (node (ref "JP5") (pin "9") (pinfunction "9_9") (pintype "passive"))
    )
    (net (code "4") (name "5VREG*") (class "Default")
      (node (ref "C9") (pin "1") (pinfunction "1_1") (pintype "passive"))
      (node (ref "IC5") (pin "1") (pinfunction "VDD_1") (pintype "bidirectional"))
      (node (ref "JP6") (pin "1") (pinfunction "1_1") (pintype "passive"))
      (node (ref "Q1") (pin "3") (pinfunction "C_3") (pintype "bidirectional"))
      (node (ref "R9") (pin "2") (pinfunction "2_2") (pintype "passive"))
    )
    (net (code "5") (name "5VREG_") (class "Default")
      (node (ref "IC6") (pin "1") (pinfunction "A0_1") (pintype "bidirectional"))
      (node (ref "IC6") (pin "16") (pinfunction "VDD_16") (pintype "bidirectional"))
      (node (ref "JP12") (pin "5") (pinfunction "5_5") (pintype "passive"))
      (node (ref "JP14") (pin "3") (pinfunction "3_3") (pintype "passive"))
      (node (ref "JP16") (pin "1") (pinfunction "1_1") (pintype "passive"))
      (node (ref "JP18") (pin "1") (pinfunction "1_1") (pintype "passive"))
      (node (ref "JP20") (pin "1") (pinfunction "1_1") (pintype "passive"))
      (node (ref "JP22") (pin "1") (pinfunction "1_1") (pintype "passive"))
      (node (ref "R11") (pin "1") (pinfunction "1_1") (pintype "passive"))
      (node (ref "R14") (pin "1") (pinfunction "1_1") (pintype "passive"))
      (node (ref "R15") (pin "1") (pinfunction "1_1") (pintype "passive"))
      (node (ref "R28") (pin "1") (pinfunction "1_1") (pintype "passive"))
      (node (ref "R29") (pin "1") (pinfunction "1_1") (pintype "passive"))
      (node (ref "S3") (pin "2") (pinfunction "2_2") (pintype "bidirectional"))
      (node (ref "S4") (pin "2") (pinfunction "2_2") (pintype "bidirectional"))
      (node (ref "SV4") (pin "1") (pinfunction "1_1") (pintype "passive"))
    )
    (net (code "6") (name "A0") (class "Default")
      (node (ref "JP8") (pin "1") (pinfunction "1_1") (pintype "passive"))
      (node (ref "U1") (pin "4") (pinfunction "A_4") (pintype "passive"))
    )
    (net (code "7") (name "A0*") (class "Default")
      (node (ref "J3") (pin "1") (pinfunction "1_1") (pintype "passive"))
      (node (ref "JP3") (pin "1") (pinfunction "1_1") (pintype "passive"))
    )
    (net (code "8") (name "A0A") (class "Default")
      (node (ref "Q3") (pin "C") (pinfunction "C1_C") (pintype "passive"))
      (node (ref "R16") (pin "2") (pinfunction "2_2") (pintype "passive"))
      (node (ref "U3") (pin "3") (pinfunction "B0_3") (pintype "passive"))
    )
    (net (code "9") (name "A0B") (class "Default")
      (node (ref "U3") (pin "1") (pinfunction "B1_1") (pintype "passive"))
      (node (ref "U9") (pin "4") (pinfunction "A_4") (pintype "passive"))
    )
    (net (code "10") (name "A0C") (class "Default")
      (node (ref "PTR1") (pin "1") (pinfunction "C_1") (pintype "passive"))
      (node (ref "R36") (pin "2") (pinfunction "2_2") (pintype "passive"))
      (node (ref "U9") (pin "3") (pinfunction "B0_3") (pintype "passive"))
    )
    (net (code "11") (name "A0D") (class "Default")
      (node (ref "Q4") (pin "C") (pinfunction "C1_C") (pintype "passive"))
      (node (ref "R18") (pin "2") (pinfunction "2_2") (pintype "passive"))
      (node (ref "U9") (pin "1") (pinfunction "B1_1") (pintype "passive"))
    )
    (net (code "12") (name "A0S") (class "Default")
      (node (ref "JP12") (pin "16") (pinfunction "16_16") (pintype "passive"))
      (node (ref "U3") (pin "4") (pinfunction "A_4") (pintype "passive"))
    )
    (net (code "13") (name "A0X") (class "Default")
      (node (ref "JP13") (pin "1") (pinfunction "1_1") (pintype "passive"))
      (node (ref "U1") (pin "3") (pinfunction "B0_3") (pintype "passive"))
    )
    (net (code "14") (name "A0Y") (class "Default")
      (node (ref "JP5") (pin "6") (pinfunction "6_6") (pintype "passive"))
      (node (ref "U1") (pin "1") (pinfunction "B1_1") (pintype "passive"))
    )
    (net (code "15") (name "A1") (class "Default")
      (node (ref "JP8") (pin "3") (pinfunction "3_3") (pintype "passive"))
      (node (ref "U2") (pin "4") (pinfunction "A_4") (pintype "passive"))
    )
    (net (code "16") (name "A1*") (class "Default")
      (node (ref "J3") (pin "2") (pinfunction "2_2") (pintype "passive"))
      (node (ref "JP3") (pin "3") (pinfunction "3_3") (pintype "passive"))
    )
    (net (code "17") (name "A1A") (class "Default")
      (node (ref "PTR2") (pin "1") (pinfunction "C_1") (pintype "passive"))
      (node (ref "R38") (pin "2") (pinfunction "2_2") (pintype "passive"))
      (node (ref "U4") (pin "3") (pinfunction "B0_3") (pintype "passive"))
    )
    (net (code "18") (name "A1B") (class "Default")
      (node (ref "PTR3") (pin "1") (pinfunction "C_1") (pintype "passive"))
      (node (ref "R40") (pin "2") (pinfunction "2_2") (pintype "passive"))
      (node (ref "U4") (pin "1") (pinfunction "B1_1") (pintype "passive"))
    )
    (net (code "19") (name "A1S") (class "Default")
      (node (ref "JP12") (pin "15") (pinfunction "15_15") (pintype "passive"))
      (node (ref "U4") (pin "4") (pinfunction "A_4") (pintype "passive"))
    )
    (net (code "20") (name "A1X") (class "Default")
      (node (ref "JP13") (pin "2") (pinfunction "2_2") (pintype "passive"))
      (node (ref "U2") (pin "3") (pinfunction "B0_3") (pintype "passive"))
    )
    (net (code "21") (name "A1Y") (class "Default")
      (node (ref "JP5") (pin "5") (pinfunction "5_5") (pintype "passive"))
      (node (ref "U2") (pin "1") (pinfunction "B1_1") (pintype "passive"))
    )
    (net (code "22") (name "A2") (class "Default")
      (node (ref "JP13") (pin "3") (pinfunction "3_3") (pintype "passive"))
      (node (ref "JP9") (pin "1") (pinfunction "1_1") (pintype "passive"))
    )
    (net (code "23") (name "A2*") (class "Default")
      (node (ref "J3") (pin "3") (pinfunction "3_3") (pintype "passive"))
      (node (ref "JP4") (pin "1") (pinfunction "1_1") (pintype "passive"))
    )
    (net (code "24") (name "A2A") (class "Default")
      (node (ref "Q5") (pin "C") (pinfunction "C1_C") (pintype "passive"))
      (node (ref "R20") (pin "2") (pinfunction "2_2") (pintype "passive"))
      (node (ref "U5") (pin "3") (pinfunction "B0_3") (pintype "passive"))
    )
    (net (code "25") (name "A2B") (class "Default")
      (node (ref "U10") (pin "4") (pinfunction "A_4") (pintype "passive"))
      (node (ref "U5") (pin "1") (pinfunction "B1_1") (pintype "passive"))
    )
    (net (code "26") (name "A2C") (class "Default")
      (node (ref "PTR4") (pin "1") (pinfunction "C_1") (pintype "passive"))
      (node (ref "R42") (pin "2") (pinfunction "2_2") (pintype "passive"))
      (node (ref "U10") (pin "3") (pinfunction "B0_3") (pintype "passive"))
    )
    (net (code "27") (name "A2D") (class "Default")
      (node (ref "PTR5") (pin "1") (pinfunction "C_1") (pintype "passive"))
      (node (ref "R44") (pin "2") (pinfunction "2_2") (pintype "passive"))
      (node (ref "U10") (pin "1") (pinfunction "B1_1") (pintype "passive"))
    )
    (net (code "28") (name "A2S") (class "Default")
      (node (ref "JP12") (pin "14") (pinfunction "14_14") (pintype "passive"))
      (node (ref "U5") (pin "4") (pinfunction "A_4") (pintype "passive"))
    )
    (net (code "29") (name "A3") (class "Default")
      (node (ref "JP13") (pin "14") (pinfunction "14_14") (pintype "passive"))
      (node (ref "JP9") (pin "2") (pinfunction "2_2") (pintype "passive"))
    )
    (net (code "30") (name "A3*") (class "Default")
      (node (ref "J3") (pin "4") (pinfunction "4_4") (pintype "passive"))
      (node (ref "JP4") (pin "2") (pinfunction "2_2") (pintype "passive"))
    )
    (net (code "31") (name "A3A") (class "Default")
      (node (ref "PTR6") (pin "1") (pinfunction "C_1") (pintype "passive"))
      (node (ref "R46") (pin "2") (pinfunction "2_2") (pintype "passive"))
      (node (ref "U6") (pin "3") (pinfunction "B0_3") (pintype "passive"))
    )
    (net (code "32") (name "A3B") (class "Default")
      (node (ref "U11") (pin "4") (pinfunction "A_4") (pintype "passive"))
      (node (ref "U6") (pin "1") (pinfunction "B1_1") (pintype "passive"))
    )
    (net (code "33") (name "A3C") (class "Default")
      (node (ref "PTR7") (pin "1") (pinfunction "C_1") (pintype "passive"))
      (node (ref "R48") (pin "2") (pinfunction "2_2") (pintype "passive"))
      (node (ref "U11") (pin "3") (pinfunction "B0_3") (pintype "passive"))
    )
    (net (code "34") (name "A3D") (class "Default")
      (node (ref "Q6") (pin "C") (pinfunction "C1_C") (pintype "passive"))
      (node (ref "R22") (pin "2") (pinfunction "2_2") (pintype "passive"))
      (node (ref "U11") (pin "1") (pinfunction "B1_1") (pintype "passive"))
    )
    (net (code "35") (name "A3S") (class "Default")
      (node (ref "JP12") (pin "3") (pinfunction "3_3") (pintype "passive"))
      (node (ref "U6") (pin "4") (pinfunction "A_4") (pintype "passive"))
    )
    (net (code "36") (name "A4") (class "Default")
      (node (ref "JP13") (pin "15") (pinfunction "15_15") (pintype "passive"))
      (node (ref "JP9") (pin "3") (pinfunction "3_3") (pintype "passive"))
    )
    (net (code "37") (name "A4*") (class "Default")
      (node (ref "J3") (pin "5") (pinfunction "5_5") (pintype "passive"))
      (node (ref "JP4") (pin "3") (pinfunction "3_3") (pintype "passive"))
    )
    (net (code "38") (name "A4A") (class "Default")
      (node (ref "PTR8") (pin "1") (pinfunction "C_1") (pintype "passive"))
      (node (ref "R50") (pin "2") (pinfunction "2_2") (pintype "passive"))
      (node (ref "U7") (pin "3") (pinfunction "B0_3") (pintype "passive"))
    )
    (net (code "39") (name "A4B") (class "Default")
      (node (ref "PTR9") (pin "1") (pinfunction "C_1") (pintype "passive"))
      (node (ref "R52") (pin "2") (pinfunction "2_2") (pintype "passive"))
      (node (ref "U7") (pin "1") (pinfunction "B1_1") (pintype "passive"))
    )
    (net (code "40") (name "A4S") (class "Default")
      (node (ref "JP12") (pin "2") (pinfunction "2_2") (pintype "passive"))
      (node (ref "U7") (pin "4") (pinfunction "A_4") (pintype "passive"))
    )
    (net (code "41") (name "A5") (class "Default")
      (node (ref "JP13") (pin "16") (pinfunction "16_16") (pintype "passive"))
      (node (ref "JP9") (pin "4") (pinfunction "4_4") (pintype "passive"))
    )
    (net (code "42") (name "A5*") (class "Default")
      (node (ref "J3") (pin "6") (pinfunction "6_6") (pintype "passive"))
      (node (ref "JP4") (pin "4") (pinfunction "4_4") (pintype "passive"))
    )
    (net (code "43") (name "A5A") (class "Default")
      (node (ref "Q7") (pin "C") (pinfunction "C1_C") (pintype "passive"))
      (node (ref "R24") (pin "2") (pinfunction "2_2") (pintype "passive"))
      (node (ref "U8") (pin "3") (pinfunction "B0_3") (pintype "passive"))
    )
    (net (code "44") (name "A5B") (class "Default")
      (node (ref "U12") (pin "4") (pinfunction "A_4") (pintype "passive"))
      (node (ref "U8") (pin "1") (pinfunction "B1_1") (pintype "passive"))
    )
    (net (code "45") (name "A5C") (class "Default")
      (node (ref "PTR10") (pin "1") (pinfunction "C_1") (pintype "passive"))
      (node (ref "R54") (pin "2") (pinfunction "2_2") (pintype "passive"))
      (node (ref "U12") (pin "3") (pinfunction "B0_3") (pintype "passive"))
    )
    (net (code "46") (name "A5D") (class "Default")
      (node (ref "Q8") (pin "C") (pinfunction "C1_C") (pintype "passive"))
      (node (ref "R26") (pin "2") (pinfunction "2_2") (pintype "passive"))
      (node (ref "U12") (pin "1") (pinfunction "B1_1") (pintype "passive"))
    )
    (net (code "47") (name "A5S") (class "Default")
      (node (ref "JP12") (pin "1") (pinfunction "1_1") (pintype "passive"))
      (node (ref "U8") (pin "4") (pinfunction "A_4") (pintype "passive"))
    )
    (net (code "48") (name "D0") (class "Default")
      (node (ref "DRV2") (pin "M0") (pinfunction "M0_M0") (pintype "bidirectional"))
      (node (ref "JP11") (pin "2") (pinfunction "2_2") (pintype "passive"))
    )
    (net (code "49") (name "D0*") (class "Default")
      (node (ref "J5") (pin "1") (pinfunction "1_1") (pintype "passive"))
      (node (ref "JP7") (pin "2") (pinfunction "2_2") (pintype "passive"))
    )
    (net (code "50") (name "D1") (class "Default")
      (node (ref "DRV2") (pin "M1") (pinfunction "M1_M1") (pintype "bidirectional"))
      (node (ref "JP11") (pin "4") (pinfunction "4_4") (pintype "passive"))
    )
    (net (code "51") (name "D1*") (class "Default")
      (node (ref "J5") (pin "2") (pinfunction "2_2") (pintype "passive"))
      (node (ref "JP7") (pin "4") (pinfunction "4_4") (pintype "passive"))
    )
    (net (code "52") (name "D2") (class "Default")
      (node (ref "DRV1") (pin "M0") (pinfunction "M0_M0") (pintype "bidirectional"))
      (node (ref "JP11") (pin "8") (pinfunction "8_8") (pintype "passive"))
    )
    (net (code "53") (name "D2*") (class "Default")
      (node (ref "J5") (pin "3") (pinfunction "3_3") (pintype "passive"))
      (node (ref "JP7") (pin "8") (pinfunction "8_8") (pintype "passive"))
    )
    (net (code "54") (name "D3") (class "Default")
      (node (ref "JP11") (pin "6") (pinfunction "6_6") (pintype "passive"))
      (node (ref "JP5") (pin "4") (pinfunction "4_4") (pintype "passive"))
    )
    (net (code "55") (name "D3*") (class "Default")
      (node (ref "J5") (pin "4") (pinfunction "4_4") (pintype "passive"))
      (node (ref "JP7") (pin "6") (pinfunction "6_6") (pintype "passive"))
    )
    (net (code "56") (name "D4") (class "Default")
      (node (ref "DRV1") (pin "M1") (pinfunction "M1_M1") (pintype "bidirectional"))
      (node (ref "JP11") (pin "7") (pinfunction "7_7") (pintype "passive"))
    )
    (net (code "57") (name "D4*") (class "Default")
      (node (ref "J5") (pin "5") (pinfunction "5_5") (pintype "passive"))
      (node (ref "JP7") (pin "7") (pinfunction "7_7") (pintype "passive"))
    )
    (net (code "58") (name "D5") (class "Default")
      (node (ref "JP11") (pin "5") (pinfunction "5_5") (pintype "passive"))
      (node (ref "JP5") (pin "3") (pinfunction "3_3") (pintype "passive"))
    )
    (net (code "59") (name "D5*") (class "Default")
      (node (ref "J5") (pin "6") (pinfunction "6_6") (pintype "passive"))
      (node (ref "JP7") (pin "5") (pinfunction "5_5") (pintype "passive"))
    )
    (net (code "60") (name "D6") (class "Default")
      (node (ref "IC1") (pin "3") (pinfunction "A_3") (pintype "bidirectional"))
      (node (ref "JP1") (pin "1") (pinfunction "1_1") (pintype "passive"))
      (node (ref "JP11") (pin "3") (pinfunction "3_3") (pintype "passive"))
    )
    (net (code "61") (name "D6*") (class "Default")
      (node (ref "J5") (pin "7") (pinfunction "7_7") (pintype "passive"))
      (node (ref "JP7") (pin "3") (pinfunction "3_3") (pintype "passive"))
    )
    (net (code "62") (name "D7*") (class "Default")
      (node (ref "J5") (pin "8") (pinfunction "8_8") (pintype "passive"))
      (node (ref "R8") (pin "2") (pinfunction "2_2") (pintype "passive"))
    )
    (net (code "63") (name "D8") (class "Default")
      (node (ref "JP10") (pin "4") (pinfunction "4_4") (pintype "passive"))
      (node (ref "JP13") (pin "10") (pinfunction "10_10") (pintype "passive"))
    )
    (net (code "64") (name "D8*") (class "Default")
      (node (ref "J4") (pin "1") (pinfunction "1_1") (pintype "passive"))
      (node (ref "JP6") (pin "4") (pinfunction "4_4") (pintype "passive"))
    )
    (net (code "65") (name "D8_") (class "Default")
      (node (ref "JP12") (pin "7") (pinfunction "7_7") (pintype "passive"))
      (node (ref "R56") (pin "2") (pinfunction "2_2") (pintype "passive"))
      (node (ref "U3") (pin "6") (pinfunction "S_6") (pintype "input"))
      (node (ref "U4") (pin "6") (pinfunction "S_6") (pintype "input"))
      (node (ref "U5") (pin "6") (pinfunction "S_6") (pintype "input"))
      (node (ref "U6") (pin "6") (pinfunction "S_6") (pintype "input"))
      (node (ref "U7") (pin "6") (pinfunction "S_6") (pintype "input"))
      (node (ref "U8") (pin "6") (pinfunction "S_6") (pintype "input"))
    )
    (net (code "66") (name "D9") (class "Default")
      (node (ref "JP10") (pin "6") (pinfunction "6_6") (pintype "passive"))
      (node (ref "JP13") (pin "7") (pinfunction "7_7") (pintype "passive"))
    )
    (net (code "67") (name "D9*") (class "Default")
      (node (ref "J4") (pin "2") (pinfunction "2_2") (pintype "passive"))
      (node (ref "JP6") (pin "6") (pinfunction "6_6") (pintype "passive"))
    )
    (net (code "68") (name "D9_") (class "Default")
      (node (ref "JP12") (pin "10") (pinfunction "10_10") (pintype "passive"))
      (node (ref "R57") (pin "2") (pinfunction "2_2") (pintype "passive"))
      (node (ref "U10") (pin "6") (pinfunction "S_6") (pintype "input"))
      (node (ref "U11") (pin "6") (pinfunction "S_6") (pintype "input"))
      (node (ref "U12") (pin "6") (pinfunction "S_6") (pintype "input"))
      (node (ref "U9") (pin "6") (pinfunction "S_6") (pintype "input"))
    )
    (net (code "69") (name "D10") (class "Default")
      (node (ref "DRV2") (pin "DIR") (pinfunction "DIR_DIR") (pintype "bidirectional"))
      (node (ref "JP10") (pin "8") (pinfunction "8_8") (pintype "passive"))
    )
    (net (code "70") (name "D10*") (class "Default")
      (node (ref "J4") (pin "3") (pinfunction "3_3") (pintype "passive"))
      (node (ref "JP6") (pin "8") (pinfunction "8_8") (pintype "passive"))
    )
    (net (code "71") (name "D11") (class "Default")
      (node (ref "DRV2") (pin "STEP") (pinfunction "STEP_STEP") (pintype "bidirectional"))
      (node (ref "JP10") (pin "10") (pinfunction "10_10") (pintype "passive"))
    )
    (net (code "72") (name "D11*") (class "Default")
      (node (ref "J4") (pin "4") (pinfunction "4_4") (pintype "passive"))
      (node (ref "JP6") (pin "10") (pinfunction "10_10") (pintype "passive"))
    )
    (net (code "73") (name "D12") (class "Default")
      (node (ref "DRV1") (pin "DIR") (pinfunction "DIR_DIR") (pintype "bidirectional"))
      (node (ref "JP10") (pin "9") (pinfunction "9_9") (pintype "passive"))
    )
    (net (code "74") (name "D12*") (class "Default")
      (node (ref "J4") (pin "5") (pinfunction "5_5") (pintype "passive"))
      (node (ref "JP6") (pin "9") (pinfunction "9_9") (pintype "passive"))
    )
    (net (code "75") (name "D13") (class "Default")
      (node (ref "DRV1") (pin "STEP") (pinfunction "STEP_STEP") (pintype "bidirectional"))
      (node (ref "JP10") (pin "7") (pinfunction "7_7") (pintype "passive"))
    )
    (net (code "76") (name "D13*") (class "Default")
      (node (ref "J4") (pin "6") (pinfunction "6_6") (pintype "passive"))
      (node (ref "JP6") (pin "7") (pinfunction "7_7") (pintype "passive"))
    )
    (net (code "77") (name "DOWNEN_") (class "Default")
      (node (ref "IC6") (pin "6") (pinfunction "P2_6") (pintype "bidirectional"))
      (node (ref "R34") (pin "2") (pinfunction "2_2") (pintype "passive"))
    )
    (net (code "78") (name "FOWEN_") (class "Default")
      (node (ref "IC6") (pin "7") (pinfunction "P3_7") (pintype "bidirectional"))
      (node (ref "R13") (pin "2") (pinfunction "2_2") (pintype "passive"))
    )
    (net (code "79") (name "GND") (class "Default")
      (node (ref "C1") (pin "2") (pinfunction "2_2") (pintype "passive"))
      (node (ref "C10") (pin "2") (pinfunction "2_2") (pintype "passive"))
      (node (ref "C11") (pin "2") (pinfunction "2_2") (pintype "passive"))
      (node (ref "C12") (pin "2") (pinfunction "2_2") (pintype "passive"))
      (node (ref "C13") (pin "2") (pinfunction "2_2") (pintype "passive"))
      (node (ref "C14") (pin "2") (pinfunction "2_2") (pintype "passive"))
      (node (ref "C15") (pin "2") (pinfunction "2_2") (pintype "passive"))
      (node (ref "C16") (pin "2") (pinfunction "2_2") (pintype "passive"))
      (node (ref "C17") (pin "2") (pinfunction "2_2") (pintype "passive"))
      (node (ref "C18") (pin "1") (pinfunction "1_1") (pintype "passive"))
      (node (ref "C19") (pin "1") (pinfunction "1_1") (pintype "passive"))
      (node (ref "C2") (pin "2") (pinfunction "2_2") (pintype "passive"))
      (node (ref "C20") (pin "1") (pinfunction "1_1") (pintype "passive"))
      (node (ref "C21") (pin "1") (pinfunction "1_1") (pintype "passive"))
      (node (ref "C22") (pin "1") (pinfunction "1_1") (pintype "passive"))
      (node (ref "C23") (pin "1") (pinfunction "1_1") (pintype "passive"))
      (node (ref "C24") (pin "1") (pinfunction "1_1") (pintype "passive"))
      (node (ref "C25") (pin "1") (pinfunction "1_1") (pintype "passive"))
      (node (ref "C26") (pin "1") (pinfunction "1_1") (pintype "passive"))
      (node (ref "C27") (pin "1") (pinfunction "1_1") (pintype "passive"))
      (node (ref "C28") (pin "1") (pinfunction "1_1") (pintype "passive"))
      (node (ref "C29") (pin "1") (pinfunction "1_1") (pintype "passive"))
      (node (ref "C3") (pin "1") (pinfunction "1_1") (pintype "bidirectional"))
      (node (ref "C30") (pin "1") (pinfunction "1_1") (pintype "passive"))
      (node (ref "C31") (pin "1") (pinfunction "1_1") (pintype "passive"))
      (node (ref "C32") (pin "1") (pinfunction "1_1") (pintype "passive"))
      (node (ref "C33") (pin "1") (pinfunction "1_1") (pintype "passive"))
      (node (ref "C4") (pin "2") (pinfunction "2_2") (pintype "passive"))
      (node (ref "C5") (pin "2") (pinfunction "2_2") (pintype "passive"))
      (node (ref "C6") (pin "2") (pinfunction "2_2") (pintype "passive"))
      (node (ref "C7") (pin "2") (pinfunction "2_2") (pintype "passive"))
      (node (ref "C8") (pin "1") (pinfunction "1_1") (pintype "bidirectional"))
      (node (ref "C9") (pin "2") (pinfunction "2_2") (pintype "passive"))
      (node (ref "D1") (pin "C") (pinfunction "C_C") (pintype "passive"))
      (node (ref "D12") (pin "C") (pinfunction "C_C") (pintype "passive"))
      (node (ref "D13") (pin "C") (pinfunction "C_C") (pintype "passive"))
      (node (ref "D14") (pin "C") (pinfunction "C_C") (pintype "passive"))
      (node (ref "D15") (pin "C") (pinfunction "C_C") (pintype "passive"))
      (node (ref "D16") (pin "C") (pinfunction "C_C") (pintype "passive"))
      (node (ref "D17") (pin "C") (pinfunction "C_C") (pintype "passive"))
      (node (ref "D3") (pin "C") (pinfunction "C_C") (pintype "passive"))
      (node (ref "DRV1") (pin "GND0") (pinfunction "GND0_GND0") (pintype "bidirectional"))
      (node (ref "DRV1") (pin "GND1") (pinfunction "GND1_GND1") (pintype "bidirectional"))
      (node (ref "DRV2") (pin "GND0") (pinfunction "GND0_GND0") (pintype "bidirectional"))
      (node (ref "DRV2") (pin "GND1") (pinfunction "GND1_GND1") (pintype "bidirectional"))
      (node (ref "IC1") (pin "2") (pinfunction "GND_2") (pintype "power_in"))
      (node (ref "IC2") (pin "1") (pinfunction "GND_1") (pintype "input"))
      (node (ref "IC3") (pin "1") (pinfunction "GND_1") (pintype "input"))
      (node (ref "IC4") (pin "2") (pinfunction "VSS_2") (pintype "bidirectional"))
      (node (ref "IC5") (pin "2") (pinfunction "VSS_2") (pintype "bidirectional"))
      (node (ref "IC6") (pin "2") (pinfunction "A1_2") (pintype "bidirectional"))
      (node (ref "IC6") (pin "3") (pinfunction "A2_3") (pintype "bidirectional"))
      (node (ref "IC6") (pin "8") (pinfunction "VSS_8") (pintype "bidirectional"))
      (node (ref "IC7") (pin "1") (pinfunction "A0_1") (pintype "bidirectional"))
      (node (ref "IC7") (pin "2") (pinfunction "A1_2") (pintype "bidirectional"))
      (node (ref "IC7") (pin "3") (pinfunction "A2_3") (pintype "bidirectional"))
      (node (ref "IC7") (pin "8") (pinfunction "VSS_8") (pintype "bidirectional"))
      (node (ref "IRLED1") (pin "2") (pinfunction "C_2") (pintype "passive"))
      (node (ref "IRLED10") (pin "2") (pinfunction "C_2") (pintype "passive"))
      (node (ref "IRLED11") (pin "2") (pinfunction "C_2") (pintype "passive"))
      (node (ref "IRLED2") (pin "2") (pinfunction "C_2") (pintype "passive"))
      (node (ref "IRLED3") (pin "2") (pinfunction "C_2") (pintype "passive"))
      (node (ref "IRLED4") (pin "2") (pinfunction "C_2") (pintype "passive"))
      (node (ref "IRLED5") (pin "2") (pinfunction "C_2") (pintype "passive"))
      (node (ref "IRLED6") (pin "2") (pinfunction "C_2") (pintype "passive"))
      (node (ref "IRLED7") (pin "2") (pinfunction "C_2") (pintype "passive"))
      (node (ref "IRLED8") (pin "2") (pinfunction "C_2") (pintype "passive"))
      (node (ref "IRLED9") (pin "2") (pinfunction "C_2") (pintype "passive"))
      (node (ref "J1") (pin "1") (pinfunction "1_1") (pintype "passive"))
      (node (ref "J2") (pin "6") (pinfunction "6_6") (pintype "passive"))
      (node (ref "J2") (pin "7") (pinfunction "7_7") (pintype "passive"))
      (node (ref "J4") (pin "7") (pinfunction "7_7") (pintype "passive"))
      (node (ref "J6") (pin "2") (pinfunction "2_2") (pintype "passive"))
      (node (ref "JP10") (pin "2") (pinfunction "2_2") (pintype "passive"))
      (node (ref "JP11") (pin "1") (pinfunction "1_1") (pintype "passive"))
      (node (ref "JP12") (pin "11") (pinfunction "11_11") (pintype "passive"))
      (node (ref "JP12") (pin "6") (pinfunction "6_6") (pintype "passive"))
      (node (ref "JP13") (pin "11") (pinfunction "11_11") (pintype "passive"))
      (node (ref "JP13") (pin "6") (pinfunction "6_6") (pintype "passive"))
      (node (ref "JP3") (pin "2") (pinfunction "2_2") (pintype "passive"))
      (node (ref "JP5") (pin "13") (pinfunction "13_13") (pintype "passive"))
      (node (ref "JP5") (pin "14") (pinfunction "14_14") (pintype "passive"))
      (node (ref "JP6") (pin "2") (pinfunction "2_2") (pintype "passive"))
      (node (ref "JP7") (pin "1") (pinfunction "1_1") (pintype "passive"))
      (node (ref "JP8") (pin "2") (pinfunction "2_2") (pintype "passive"))
      (node (ref "LS1") (pin "+") (pinfunction "1_+") (pintype "passive"))
      (node (ref "PLED1") (pin "2") (pinfunction "VSS_2") (pintype "bidirectional"))
      (node (ref "PLED2") (pin "2") (pinfunction "VSS_2") (pintype "bidirectional"))
      (node (ref "PLED3") (pin "2") (pinfunction "VSS_2") (pintype "bidirectional"))
      (node (ref "PLED4") (pin "2") (pinfunction "VSS_2") (pintype "bidirectional"))
      (node (ref "PLED5") (pin "2") (pinfunction "VSS_2") (pintype "bidirectional"))
      (node (ref "PLED6") (pin "2") (pinfunction "VSS_2") (pintype "bidirectional"))
      (node (ref "PLED7") (pin "2") (pinfunction "VSS_2") (pintype "bidirectional"))
      (node (ref "PLED8") (pin "2") (pinfunction "VSS_2") (pintype "bidirectional"))
      (node (ref "PLED9") (pin "2") (pinfunction "VSS_2") (pintype "bidirectional"))
      (node (ref "PTR1") (pin "2") (pinfunction "E_2") (pintype "passive"))
      (node (ref "PTR10") (pin "2") (pinfunction "E_2") (pintype "passive"))
      (node (ref "PTR2") (pin "2") (pinfunction "E_2") (pintype "passive"))
      (node (ref "PTR3") (pin "2") (pinfunction "E_2") (pintype "passive"))
      (node (ref "PTR4") (pin "2") (pinfunction "E_2") (pintype "passive"))
      (node (ref "PTR5") (pin "2") (pinfunction "E_2") (pintype "passive"))
      (node (ref "PTR6") (pin "2") (pinfunction "E_2") (pintype "passive"))
      (node (ref "PTR7") (pin "2") (pinfunction "E_2") (pintype "passive"))
      (node (ref "PTR8") (pin "2") (pinfunction "E_2") (pintype "passive"))
      (node (ref "PTR9") (pin "2") (pinfunction "E_2") (pintype "passive"))
      (node (ref "Q3") (pin "E") (pinfunction "E1_E") (pintype "passive"))
      (node (ref "Q4") (pin "E") (pinfunction "E1_E") (pintype "passive"))
      (node (ref "Q5") (pin "E") (pinfunction "E1_E") (pintype "passive"))
      (node (ref "Q6") (pin "E") (pinfunction "E1_E") (pintype "passive"))
      (node (ref "Q7") (pin "E") (pinfunction "E1_E") (pintype "passive"))
      (node (ref "Q8") (pin "E") (pinfunction "E1_E") (pintype "passive"))
      (node (ref "R10") (pin "2") (pinfunction "2_2") (pintype "passive"))
      (node (ref "R12") (pin "1") (pinfunction "1_1") (pintype "passive"))
      (node (ref "R2") (pin "2") (pinfunction "2_2") (pintype "passive"))
      (node (ref "R3") (pin "1") (pinfunction "1_1") (pintype "passive"))
      (node (ref "R4") (pin "1") (pinfunction "1_1") (pintype "passive"))
      (node (ref "R5") (pin "1") (pinfunction "1_1") (pintype "passive"))
      (node (ref "R56") (pin "1") (pinfunction "1_1") (pintype "passive"))
      (node (ref "R57") (pin "1") (pinfunction "1_1") (pintype "passive"))
      (node (ref "R6") (pin "1") (pinfunction "1_1") (pintype "passive"))
      (node (ref "S3") (pin "3") (pinfunction "3_3") (pintype "bidirectional"))
      (node (ref "S4") (pin "3") (pinfunction "3_3") (pintype "bidirectional"))
      (node (ref "SV3") (pin "1") (pinfunction "1_1") (pintype "passive"))
      (node (ref "SV4") (pin "2") (pinfunction "2_2") (pintype "passive"))
      (node (ref "U1") (pin "2") (pinfunction "GND_2") (pintype "passive"))
      (node (ref "U10") (pin "2") (pinfunction "GND_2") (pintype "passive"))
      (node (ref "U11") (pin "2") (pinfunction "GND_2") (pintype "passive"))
      (node (ref "U12") (pin "2") (pinfunction "GND_2") (pintype "passive"))
      (node (ref "U2") (pin "2") (pinfunction "GND_2") (pintype "passive"))
      (node (ref "U3") (pin "2") (pinfunction "GND_2") (pintype "passive"))
      (node (ref "U4") (pin "2") (pinfunction "GND_2") (pintype "passive"))
      (node (ref "U5") (pin "2") (pinfunction "GND_2") (pintype "passive"))
      (node (ref "U6") (pin "2") (pinfunction "GND_2") (pintype "passive"))
      (node (ref "U7") (pin "2") (pinfunction "GND_2") (pintype "passive"))
      (node (ref "U8") (pin "2") (pinfunction "GND_2") (pintype "passive"))
      (node (ref "U9") (pin "2") (pinfunction "GND_2") (pintype "passive"))
    )
    (net (code "80") (name "MOTL_EN") (class "Default")
      (node (ref "DRV2") (pin "EN") (pinfunction "EN_EN") (pintype "bidirectional"))
      (node (ref "IC7") (pin "4") (pinfunction "P0_4") (pintype "bidirectional"))
    )
    (net (code "81") (name "MOTR_EN") (class "Default")
      (node (ref "DRV1") (pin "EN") (pinfunction "EN_EN") (pintype "bidirectional"))
      (node (ref "IC7") (pin "5") (pinfunction "P1_5") (pintype "bidirectional"))
    )
    (net (code "82") (name "MUL0") (class "Default")
      (node (ref "IC7") (pin "6") (pinfunction "P2_6") (pintype "bidirectional"))
      (node (ref "R12") (pin "2") (pinfunction "2_2") (pintype "passive"))
      (node (ref "U1") (pin "6") (pinfunction "S_6") (pintype "input"))
      (node (ref "U2") (pin "6") (pinfunction "S_6") (pintype "input"))
    )
    (net (code "83") (name "Net-(C18-Pad2)") (class "Default")
      (node (ref "C18") (pin "2") (pinfunction "2_2") (pintype "passive"))
      (node (ref "C19") (pin "2") (pinfunction "2_2") (pintype "passive"))
      (node (ref "C20") (pin "2") (pinfunction "2_2") (pintype "passive"))
      (node (ref "C21") (pin "2") (pinfunction "2_2") (pintype "passive"))
      (node (ref "C22") (pin "2") (pinfunction "2_2") (pintype "passive"))
      (node (ref "C23") (pin "2") (pinfunction "2_2") (pintype "passive"))
      (node (ref "JP19") (pin "2") (pinfunction "2_2") (pintype "passive"))
      (node (ref "R16") (pin "1") (pinfunction "1_1") (pintype "passive"))
      (node (ref "R18") (pin "1") (pinfunction "1_1") (pintype "passive"))
      (node (ref "R20") (pin "1") (pinfunction "1_1") (pintype "passive"))
      (node (ref "R22") (pin "1") (pinfunction "1_1") (pintype "passive"))
      (node (ref "R24") (pin "1") (pinfunction "1_1") (pintype "passive"))
      (node (ref "R26") (pin "1") (pinfunction "1_1") (pintype "passive"))
    )
    (net (code "84") (name "Net-(C24-Pad2)") (class "Default")
      (node (ref "C24") (pin "2") (pinfunction "2_2") (pintype "passive"))
      (node (ref "C25") (pin "2") (pinfunction "2_2") (pintype "passive"))
      (node (ref "C26") (pin "2") (pinfunction "2_2") (pintype "passive"))
      (node (ref "C27") (pin "2") (pinfunction "2_2") (pintype "passive"))
      (node (ref "C28") (pin "2") (pinfunction "2_2") (pintype "passive"))
      (node (ref "C29") (pin "2") (pinfunction "2_2") (pintype "passive"))
      (node (ref "C30") (pin "2") (pinfunction "2_2") (pintype "passive"))
      (node (ref "C31") (pin "2") (pinfunction "2_2") (pintype "passive"))
      (node (ref "C32") (pin "2") (pinfunction "2_2") (pintype "passive"))
      (node (ref "C33") (pin "2") (pinfunction "2_2") (pintype "passive"))
      (node (ref "JP23") (pin "2") (pinfunction "2_2") (pintype "passive"))
      (node (ref "R36") (pin "1") (pinfunction "1_1") (pintype "passive"))
      (node (ref "R38") (pin "1") (pinfunction "1_1") (pintype "passive"))
      (node (ref "R40") (pin "1") (pinfunction "1_1") (pintype "passive"))
      (node (ref "R42") (pin "1") (pinfunction "1_1") (pintype "passive"))
      (node (ref "R44") (pin "1") (pinfunction "1_1") (pintype "passive"))
      (node (ref "R46") (pin "1") (pinfunction "1_1") (pintype "passive"))
      (node (ref "R48") (pin "1") (pinfunction "1_1") (pintype "passive"))
      (node (ref "R50") (pin "1") (pinfunction "1_1") (pintype "passive"))
      (node (ref "R52") (pin "1") (pinfunction "1_1") (pintype "passive"))
      (node (ref "R54") (pin "1") (pinfunction "1_1") (pintype "passive"))
    )
    (net (code "85") (name "Net-(D1-PadA)") (class "Default")
      (node (ref "D1") (pin "A") (pinfunction "A_A") (pintype "passive"))
      (node (ref "R7") (pin "2") (pinfunction "2_2") (pintype "passive"))
    )
    (net (code "86") (name "Net-(D2-PadC)") (class "Default")
      (node (ref "D2") (pin "C") (pinfunction "C_C") (pintype "passive"))
      (node (ref "JP8") (pin "4") (pinfunction "4_4") (pintype "passive"))
    )
    (net (code "87") (name "Net-(D3-PadA)") (class "Default")
      (node (ref "D3") (pin "A") (pinfunction "A_A") (pintype "passive"))
      (node (ref "R11") (pin "2") (pinfunction "2_2") (pintype "passive"))
    )
    (net (code "88") (name "Net-(D4-PadA)") (class "Default")
      (node (ref "D4") (pin "A") (pinfunction "A_A") (pintype "passive"))
      (node (ref "R14") (pin "2") (pinfunction "2_2") (pintype "passive"))
    )
    (net (code "89") (name "Net-(D5-PadA)") (class "Default")
      (node (ref "D5") (pin "A") (pinfunction "A_A") (pintype "passive"))
      (node (ref "R15") (pin "2") (pinfunction "2_2") (pintype "passive"))
    )
    (net (code "90") (name "Net-(D6-PadA)") (class "Default")
      (node (ref "D6") (pin "A") (pinfunction "A_A") (pintype "passive"))
      (node (ref "R28") (pin "2") (pinfunction "2_2") (pintype "passive"))
    )
    (net (code "91") (name "Net-(D7-PadA)") (class "Default")
      (node (ref "D7") (pin "A") (pinfunction "A_A") (pintype "passive"))
      (node (ref "R29") (pin "2") (pinfunction "2_2") (pintype "passive"))
    )
    (net (code "92") (name "Net-(D8-PadA)") (class "Default")
      (node (ref "D8") (pin "A") (pinfunction "A_A") (pintype "passive"))
      (node (ref "R30") (pin "2") (pinfunction "2_2") (pintype "passive"))
    )
    (net (code "93") (name "Net-(D9-PadA)") (class "Default")
      (node (ref "D9") (pin "A") (pinfunction "A_A") (pintype "passive"))
      (node (ref "R31") (pin "2") (pinfunction "2_2") (pintype "passive"))
    )
    (net (code "94") (name "Net-(D10-PadA)") (class "Default")
      (node (ref "D10") (pin "A") (pinfunction "A_A") (pintype "passive"))
      (node (ref "R32") (pin "2") (pinfunction "2_2") (pintype "passive"))
    )
    (net (code "95") (name "Net-(D11-PadA)") (class "Default")
      (node (ref "D11") (pin "A") (pinfunction "A_A") (pintype "passive"))
      (node (ref "R33") (pin "2") (pinfunction "2_2") (pintype "passive"))
    )
    (net (code "96") (name "Net-(D12-PadA)") (class "Default")
      (node (ref "D12") (pin "A") (pinfunction "A_A") (pintype "passive"))
      (node (ref "R17") (pin "2") (pinfunction "2_2") (pintype "passive"))
    )
    (net (code "97") (name "Net-(D13-PadA)") (class "Default")
      (node (ref "D13") (pin "A") (pinfunction "A_A") (pintype "passive"))
      (node (ref "R19") (pin "2") (pinfunction "2_2") (pintype "passive"))
    )
    (net (code "98") (name "Net-(D14-PadA)") (class "Default")
      (node (ref "D14") (pin "A") (pinfunction "A_A") (pintype "passive"))
      (node (ref "R21") (pin "2") (pinfunction "2_2") (pintype "passive"))
    )
    (net (code "99") (name "Net-(D15-PadA)") (class "Default")
      (node (ref "D15") (pin "A") (pinfunction "A_A") (pintype "passive"))
      (node (ref "R23") (pin "2") (pinfunction "2_2") (pintype "passive"))
    )
    (net (code "100") (name "Net-(D16-PadA)") (class "Default")
      (node (ref "D16") (pin "A") (pinfunction "A_A") (pintype "passive"))
      (node (ref "R25") (pin "2") (pinfunction "2_2") (pintype "passive"))
    )
    (net (code "101") (name "Net-(D17-PadA)") (class "Default")
      (node (ref "D17") (pin "A") (pinfunction "A_A") (pintype "passive"))
      (node (ref "R27") (pin "2") (pinfunction "2_2") (pintype "passive"))
    )
    (net (code "102") (name "Net-(DRV1-PadA1)") (class "Default")
      (node (ref "DRV1") (pin "A1") (pinfunction "A1_A1") (pintype "bidirectional"))
      (node (ref "SV1") (pin "3") (pinfunction "3_3") (pintype "passive"))
    )
    (net (code "103") (name "Net-(DRV1-PadA2)") (class "Default")
      (node (ref "DRV1") (pin "A2") (pinfunction "A2_A2") (pintype "bidirectional"))
      (node (ref "SV1") (pin "4") (pinfunction "4_4") (pintype "passive"))
    )
    (net (code "104") (name "Net-(DRV1-PadB1)") (class "Default")
      (node (ref "DRV1") (pin "B1") (pinfunction "B1_B1") (pintype "bidirectional"))
      (node (ref "SV1") (pin "2") (pinfunction "2_2") (pintype "passive"))
    )
    (net (code "105") (name "Net-(DRV1-PadB2)") (class "Default")
      (node (ref "DRV1") (pin "B2") (pinfunction "B2_B2") (pintype "bidirectional"))
      (node (ref "SV1") (pin "1") (pinfunction "1_1") (pintype "passive"))
    )
    (net (code "106") (name "Net-(DRV2-PadA1)") (class "Default")
      (node (ref "DRV2") (pin "A1") (pinfunction "A1_A1") (pintype "bidirectional"))
      (node (ref "SV2") (pin "3") (pinfunction "3_3") (pintype "passive"))
    )
    (net (code "107") (name "Net-(DRV2-PadA2)") (class "Default")
      (node (ref "DRV2") (pin "A2") (pinfunction "A2_A2") (pintype "bidirectional"))
      (node (ref "SV2") (pin "4") (pinfunction "4_4") (pintype "passive"))
    )
    (net (code "108") (name "Net-(DRV2-PadB1)") (class "Default")
      (node (ref "DRV2") (pin "B1") (pinfunction "B1_B1") (pintype "bidirectional"))
      (node (ref "SV2") (pin "2") (pinfunction "2_2") (pintype "passive"))
    )
    (net (code "109") (name "Net-(DRV2-PadB2)") (class "Default")
      (node (ref "DRV2") (pin "B2") (pinfunction "B2_B2") (pintype "bidirectional"))
      (node (ref "SV2") (pin "1") (pinfunction "1_1") (pintype "passive"))
    )
    (net (code "110") (name "Net-(F1-1)") (class "Default")
      (node (ref "F1") (pin "P$1") (pinfunction "1_P$1") (pintype "bidirectional"))
      (node (ref "S1") (pin "3") (pinfunction "3_3") (pintype "bidirectional"))
      (node (ref "SJ1") (pin "1") (pinfunction "1_1") (pintype "passive"))
    )
    (net (code "111") (name "Net-(IC1-B)") (class "Default")
      (node (ref "IC1") (pin "4") (pinfunction "B_4") (pintype "bidirectional"))
      (node (ref "JP1") (pin "2") (pinfunction "2_2") (pintype "passive"))
      (node (ref "PLED1") (pin "3") (pinfunction "DI_3") (pintype "bidirectional"))
    )
    (net (code "112") (name "Net-(IC4-AIN)") (class "Default")
      (node (ref "IC4") (pin "3") (pinfunction "AIN_3") (pintype "bidirectional"))
      (node (ref "R1") (pin "2") (pinfunction "2_2") (pintype "passive"))
      (node (ref "R2") (pin "1") (pinfunction "1_1") (pintype "passive"))
    )
    (net (code "113") (name "Net-(IC5-AIN)") (class "Default")
      (node (ref "IC5") (pin "3") (pinfunction "AIN_3") (pintype "bidirectional"))
      (node (ref "R9") (pin "1") (pinfunction "1_1") (pintype "passive"))
      (node (ref "S2") (pin "5") (pinfunction "COMMON_5") (pintype "bidirectional"))
    )
    (net (code "114") (name "Net-(IC6-P4)") (class "Default")
      (node (ref "D7") (pin "C") (pinfunction "C_C") (pintype "passive"))
      (node (ref "IC6") (pin "9") (pinfunction "P4_9") (pintype "bidirectional"))
    )
    (net (code "115") (name "Net-(IC6-P5)") (class "Default")
      (node (ref "D5") (pin "C") (pinfunction "C_C") (pintype "passive"))
      (node (ref "IC6") (pin "10") (pinfunction "P5_10") (pintype "bidirectional"))
    )
    (net (code "116") (name "Net-(IC6-P6)") (class "Default")
      (node (ref "D6") (pin "C") (pinfunction "C_C") (pintype "passive"))
      (node (ref "IC6") (pin "11") (pinfunction "P6_11") (pintype "bidirectional"))
    )
    (net (code "117") (name "Net-(IC6-P7)") (class "Default")
      (node (ref "D4") (pin "C") (pinfunction "C_C") (pintype "passive"))
      (node (ref "IC6") (pin "12") (pinfunction "P7_12") (pintype "bidirectional"))
    )
    (net (code "118") (name "Net-(IC7-P4)") (class "Default")
      (node (ref "D9") (pin "C") (pinfunction "C_C") (pintype "passive"))
      (node (ref "IC7") (pin "9") (pinfunction "P4_9") (pintype "bidirectional"))
    )
    (net (code "119") (name "Net-(IC7-P5)") (class "Default")
      (node (ref "D11") (pin "C") (pinfunction "C_C") (pintype "passive"))
      (node (ref "IC7") (pin "10") (pinfunction "P5_10") (pintype "bidirectional"))
    )
    (net (code "120") (name "Net-(IC7-P6)") (class "Default")
      (node (ref "D8") (pin "C") (pinfunction "C_C") (pintype "passive"))
      (node (ref "IC7") (pin "11") (pinfunction "P6_11") (pintype "bidirectional"))
    )
    (net (code "121") (name "Net-(IC7-P7)") (class "Default")
      (node (ref "D10") (pin "C") (pinfunction "C_C") (pintype "passive"))
      (node (ref "IC7") (pin "12") (pinfunction "P7_12") (pintype "bidirectional"))
    )
    (net (code "122") (name "Net-(IRLED1-A)") (class "Default")
      (node (ref "IRLED1") (pin "1") (pinfunction "A_1") (pintype "passive"))
      (node (ref "R35") (pin "2") (pinfunction "2_2") (pintype "passive"))
    )
    (net (code "123") (name "Net-(IRLED2-A)") (class "Default")
      (node (ref "IRLED2") (pin "1") (pinfunction "A_1") (pintype "passive"))
      (node (ref "R37") (pin "2") (pinfunction "2_2") (pintype "passive"))
    )
    (net (code "124") (name "Net-(IRLED3-A)") (class "Default")
      (node (ref "IRLED3") (pin "1") (pinfunction "A_1") (pintype "passive"))
      (node (ref "R39") (pin "2") (pinfunction "2_2") (pintype "passive"))
    )
    (net (code "125") (name "Net-(IRLED4-A)") (class "Default")
      (node (ref "IRLED4") (pin "1") (pinfunction "A_1") (pintype "passive"))
      (node (ref "R41") (pin "2") (pinfunction "2_2") (pintype "passive"))
    )
    (net (code "126") (name "Net-(IRLED5-A)") (class "Default")
      (node (ref "IRLED5") (pin "1") (pinfunction "A_1") (pintype "passive"))
      (node (ref "R43") (pin "2") (pinfunction "2_2") (pintype "passive"))
    )
    (net (code "127") (name "Net-(IRLED6-A)") (class "Default")
      (node (ref "IRLED6") (pin "1") (pinfunction "A_1") (pintype "passive"))
      (node (ref "R45") (pin "2") (pinfunction "2_2") (pintype "passive"))
    )
    (net (code "128") (name "Net-(IRLED7-A)") (class "Default")
      (node (ref "IRLED7") (pin "1") (pinfunction "A_1") (pintype "passive"))
      (node (ref "R47") (pin "2") (pinfunction "2_2") (pintype "passive"))
    )
    (net (code "129") (name "Net-(IRLED8-A)") (class "Default")
      (node (ref "IRLED8") (pin "1") (pinfunction "A_1") (pintype "passive"))
      (node (ref "R49") (pin "2") (pinfunction "2_2") (pintype "passive"))
    )
    (net (code "130") (name "Net-(IRLED9-A)") (class "Default")
      (node (ref "IRLED9") (pin "1") (pinfunction "A_1") (pintype "passive"))
      (node (ref "R51") (pin "2") (pinfunction "2_2") (pintype "passive"))
    )
    (net (code "131") (name "Net-(IRLED10-A)") (class "Default")
      (node (ref "IRLED10") (pin "1") (pinfunction "A_1") (pintype "passive"))
      (node (ref "R53") (pin "2") (pinfunction "2_2") (pintype "passive"))
    )
    (net (code "132") (name "Net-(IRLED11-A)") (class "Default")
      (node (ref "IRLED11") (pin "1") (pinfunction "A_1") (pintype "passive"))
      (node (ref "R55") (pin "2") (pinfunction "2_2") (pintype "passive"))
    )
    (net (code "133") (name "Net-(J1-Pad2)") (class "Default")
      (node (ref "J1") (pin "2") (pinfunction "2_2") (pintype "passive"))
      (node (ref "S1") (pin "2") (pinfunction "2_2") (pintype "bidirectional"))
    )
    (net (code "134") (name "Net-(JP18-Pad2)") (class "Default")
      (node (ref "JP18") (pin "2") (pinfunction "2_2") (pintype "passive"))
      (node (ref "JP19") (pin "1") (pinfunction "1_1") (pintype "passive"))
    )
    (net (code "135") (name "Net-(JP22-Pad2)") (class "Default")
      (node (ref "JP22") (pin "2") (pinfunction "2_2") (pintype "passive"))
      (node (ref "JP23") (pin "1") (pinfunction "1_1") (pintype "passive"))
    )
    (net (code "136") (name "Net-(LS1-2)") (class "Default")
      (node (ref "LS1") (pin "-") (pinfunction "2_-") (pintype "passive"))
      (node (ref "Q1") (pin "2") (pinfunction "E_2") (pintype "bidirectional"))
    )
    (net (code "137") (name "Net-(PLED1-DO)") (class "Default")
      (node (ref "PLED1") (pin "1") (pinfunction "DO_1") (pintype "bidirectional"))
      (node (ref "PLED2") (pin "3") (pinfunction "DI_3") (pintype "bidirectional"))
    )
    (net (code "138") (name "Net-(PLED1-VDD)") (class "Default")
      (node (ref "C10") (pin "1") (pinfunction "1_1") (pintype "passive"))
      (node (ref "C11") (pin "1") (pinfunction "1_1") (pintype "passive"))
      (node (ref "C12") (pin "1") (pinfunction "1_1") (pintype "passive"))
      (node (ref "C13") (pin "1") (pinfunction "1_1") (pintype "passive"))
      (node (ref "C14") (pin "1") (pinfunction "1_1") (pintype "passive"))
      (node (ref "C15") (pin "1") (pinfunction "1_1") (pintype "passive"))
      (node (ref "C16") (pin "1") (pinfunction "1_1") (pintype "passive"))
      (node (ref "C17") (pin "1") (pinfunction "1_1") (pintype "passive"))
      (node (ref "C7") (pin "1") (pinfunction "1_1") (pintype "passive"))
      (node (ref "JP2") (pin "1") (pinfunction "1_1") (pintype "passive"))
      (node (ref "PLED1") (pin "4") (pinfunction "VDD_4") (pintype "bidirectional"))
      (node (ref "PLED2") (pin "4") (pinfunction "VDD_4") (pintype "bidirectional"))
      (node (ref "PLED3") (pin "4") (pinfunction "VDD_4") (pintype "bidirectional"))
      (node (ref "PLED4") (pin "4") (pinfunction "VDD_4") (pintype "bidirectional"))
      (node (ref "PLED5") (pin "4") (pinfunction "VDD_4") (pintype "bidirectional"))
      (node (ref "PLED6") (pin "4") (pinfunction "VDD_4") (pintype "bidirectional"))
      (node (ref "PLED7") (pin "4") (pinfunction "VDD_4") (pintype "bidirectional"))
      (node (ref "PLED8") (pin "4") (pinfunction "VDD_4") (pintype "bidirectional"))
      (node (ref "PLED9") (pin "4") (pinfunction "VDD_4") (pintype "bidirectional"))
    )
    (net (code "139") (name "Net-(PLED2-DO)") (class "Default")
      (node (ref "PLED2") (pin "1") (pinfunction "DO_1") (pintype "bidirectional"))
      (node (ref "PLED3") (pin "3") (pinfunction "DI_3") (pintype "bidirectional"))
    )
    (net (code "140") (name "Net-(PLED3-DO)") (class "Default")
      (node (ref "PLED3") (pin "1") (pinfunction "DO_1") (pintype "bidirectional"))
      (node (ref "PLED4") (pin "3") (pinfunction "DI_3") (pintype "bidirectional"))
    )
    (net (code "141") (name "Net-(PLED4-DO)") (class "Default")
      (node (ref "PLED4") (pin "1") (pinfunction "DO_1") (pintype "bidirectional"))
      (node (ref "PLED5") (pin "3") (pinfunction "DI_3") (pintype "bidirectional"))
    )
    (net (code "142") (name "Net-(PLED5-DO)") (class "Default")
      (node (ref "PLED5") (pin "1") (pinfunction "DO_1") (pintype "bidirectional"))
      (node (ref "PLED6") (pin "3") (pinfunction "DI_3") (pintype "bidirectional"))
    )
    (net (code "143") (name "Net-(PLED6-DO)") (class "Default")
      (node (ref "PLED6") (pin "1") (pinfunction "DO_1") (pintype "bidirectional"))
      (node (ref "PLED7") (pin "3") (pinfunction "DI_3") (pintype "bidirectional"))
    )
    (net (code "144") (name "Net-(PLED7-DO)") (class "Default")
      (node (ref "PLED7") (pin "1") (pinfunction "DO_1") (pintype "bidirectional"))
      (node (ref "PLED8") (pin "3") (pinfunction "DI_3") (pintype "bidirectional"))
    )
    (net (code "145") (name "Net-(PLED8-DO)") (class "Default")
      (node (ref "PLED8") (pin "1") (pinfunction "DO_1") (pintype "bidirectional"))
      (node (ref "PLED9") (pin "3") (pinfunction "DI_3") (pintype "bidirectional"))
    )
    (net (code "146") (name "Net-(Q1-B)") (class "Default")
      (node (ref "Q1") (pin "1") (pinfunction "B_1") (pintype "bidirectional"))
      (node (ref "R8") (pin "1") (pinfunction "1_1") (pintype "passive"))
    )
    (net (code "147") (name "Net-(Q2-B)") (class "Default")
      (node (ref "Q2") (pin "1") (pinfunction "B_1") (pintype "bidirectional"))
      (node (ref "R13") (pin "1") (pinfunction "1_1") (pintype "passive"))
    )
    (net (code "148") (name "Net-(Q2-C)") (class "Default")
      (node (ref "JP16") (pin "3") (pinfunction "3_3") (pintype "passive"))
      (node (ref "JP17") (pin "2") (pinfunction "2_2") (pintype "passive"))
      (node (ref "Q2") (pin "3") (pinfunction "C_3") (pintype "bidirectional"))
    )
    (net (code "149") (name "Net-(Q2-E)") (class "Default")
      (node (ref "JP17") (pin "1") (pinfunction "1_1") (pintype "passive"))
      (node (ref "Q2") (pin "2") (pinfunction "E_2") (pintype "bidirectional"))
      (node (ref "R17") (pin "1") (pinfunction "1_1") (pintype "passive"))
      (node (ref "R19") (pin "1") (pinfunction "1_1") (pintype "passive"))
      (node (ref "R21") (pin "1") (pinfunction "1_1") (pintype "passive"))
      (node (ref "R23") (pin "1") (pinfunction "1_1") (pintype "passive"))
      (node (ref "R25") (pin "1") (pinfunction "1_1") (pintype "passive"))
      (node (ref "R27") (pin "1") (pinfunction "1_1") (pintype "passive"))
    )
    (net (code "150") (name "Net-(Q9-B)") (class "Default")
      (node (ref "Q9") (pin "1") (pinfunction "B_1") (pintype "bidirectional"))
      (node (ref "R34") (pin "1") (pinfunction "1_1") (pintype "passive"))
    )
    (net (code "151") (name "Net-(Q9-C)") (class "Default")
      (node (ref "JP20") (pin "3") (pinfunction "3_3") (pintype "passive"))
      (node (ref "JP21") (pin "2") (pinfunction "2_2") (pintype "passive"))
      (node (ref "Q9") (pin "3") (pinfunction "C_3") (pintype "bidirectional"))
    )
    (net (code "152") (name "Net-(Q9-E)") (class "Default")
      (node (ref "JP21") (pin "1") (pinfunction "1_1") (pintype "passive"))
      (node (ref "Q9") (pin "2") (pinfunction "E_2") (pintype "bidirectional"))
      (node (ref "R35") (pin "1") (pinfunction "1_1") (pintype "passive"))
      (node (ref "R37") (pin "1") (pinfunction "1_1") (pintype "passive"))
      (node (ref "R39") (pin "1") (pinfunction "1_1") (pintype "passive"))
      (node (ref "R41") (pin "1") (pinfunction "1_1") (pintype "passive"))
      (node (ref "R43") (pin "1") (pinfunction "1_1") (pintype "passive"))
      (node (ref "R45") (pin "1") (pinfunction "1_1") (pintype "passive"))
      (node (ref "R47") (pin "1") (pinfunction "1_1") (pintype "passive"))
      (node (ref "R49") (pin "1") (pinfunction "1_1") (pintype "passive"))
      (node (ref "R51") (pin "1") (pinfunction "1_1") (pintype "passive"))
      (node (ref "R53") (pin "1") (pinfunction "1_1") (pintype "passive"))
      (node (ref "R55") (pin "1") (pinfunction "1_1") (pintype "passive"))
    )
    (net (code "153") (name "Net-(S2-A)") (class "Default")
      (node (ref "R5") (pin "2") (pinfunction "2_2") (pintype "passive"))
      (node (ref "S2") (pin "1") (pinfunction "A_1") (pintype "bidirectional"))
    )
    (net (code "154") (name "Net-(S2-B)") (class "Default")
      (node (ref "R6") (pin "2") (pinfunction "2_2") (pintype "passive"))
      (node (ref "S2") (pin "4") (pinfunction "B_4") (pintype "bidirectional"))
    )
    (net (code "155") (name "Net-(S2-C)") (class "Default")
      (node (ref "R3") (pin "2") (pinfunction "2_2") (pintype "passive"))
      (node (ref "S2") (pin "3") (pinfunction "C_3") (pintype "bidirectional"))
    )
    (net (code "156") (name "Net-(S2-CENTER)") (class "Default")
      (node (ref "R4") (pin "2") (pinfunction "2_2") (pintype "passive"))
      (node (ref "S2") (pin "2") (pinfunction "CENTER_2") (pintype "bidirectional"))
    )
    (net (code "157") (name "Net-(S2-D)") (class "Default")
      (node (ref "R10") (pin "1") (pinfunction "1_1") (pintype "passive"))
      (node (ref "S2") (pin "6") (pinfunction "D_6") (pintype "bidirectional"))
    )
    (net (code "158") (name "SCL") (class "Default")
      (node (ref "IC4") (pin "5") (pinfunction "SCL_5") (pintype "bidirectional"))
      (node (ref "IC7") (pin "14") (pinfunction "SCL_14") (pintype "bidirectional"))
      (node (ref "JP10") (pin "3") (pinfunction "3_3") (pintype "passive"))
      (node (ref "JP13") (pin "9") (pinfunction "9_9") (pintype "passive"))
      (node (ref "JP5") (pin "2") (pinfunction "2_2") (pintype "passive"))
      (node (ref "SV3") (pin "3") (pinfunction "3_3") (pintype "passive"))
    )
    (net (code "159") (name "SCL*") (class "Default")
      (node (ref "IC5") (pin "5") (pinfunction "SCL_5") (pintype "bidirectional"))
      (node (ref "J4") (pin "10") (pinfunction "10_10") (pintype "passive"))
      (node (ref "JP6") (pin "3") (pinfunction "3_3") (pintype "passive"))
    )
    (net (code "160") (name "SCL_") (class "Default")
      (node (ref "IC6") (pin "14") (pinfunction "SCL_14") (pintype "bidirectional"))
      (node (ref "JP12") (pin "8") (pinfunction "8_8") (pintype "passive"))
      (node (ref "SV4") (pin "3") (pinfunction "3_3") (pintype "passive"))
    )
    (net (code "161") (name "SDA") (class "Default")
      (node (ref "IC4") (pin "4") (pinfunction "SDA_4") (pintype "bidirectional"))
      (node (ref "IC7") (pin "15") (pinfunction "SDA_15") (pintype "bidirectional"))
      (node (ref "JP10") (pin "5") (pinfunction "5_5") (pintype "passive"))
      (node (ref "JP13") (pin "8") (pinfunction "8_8") (pintype "passive"))
      (node (ref "JP5") (pin "1") (pinfunction "1_1") (pintype "passive"))
      (node (ref "SV3") (pin "4") (pinfunction "4_4") (pintype "passive"))
    )
    (net (code "162") (name "SDA*") (class "Default")
      (node (ref "IC5") (pin "4") (pinfunction "SDA_4") (pintype "bidirectional"))
      (node (ref "J4") (pin "9") (pinfunction "9_9") (pintype "passive"))
      (node (ref "JP6") (pin "5") (pinfunction "5_5") (pintype "passive"))
    )
    (net (code "163") (name "SDA_") (class "Default")
      (node (ref "IC6") (pin "15") (pinfunction "SDA_15") (pintype "bidirectional"))
      (node (ref "JP12") (pin "9") (pinfunction "9_9") (pintype "passive"))
      (node (ref "SV4") (pin "4") (pinfunction "4_4") (pintype "passive"))
    )
    (net (code "164") (name "SW0_") (class "Default")
      (node (ref "IC6") (pin "4") (pinfunction "P0_4") (pintype "bidirectional"))
      (node (ref "S3") (pin "1") (pinfunction "1_1") (pintype "bidirectional"))
    )
    (net (code "165") (name "SW1_") (class "Default")
      (node (ref "IC6") (pin "5") (pinfunction "P1_5") (pintype "bidirectional"))
      (node (ref "S4") (pin "1") (pinfunction "1_1") (pintype "bidirectional"))
    )
    (net (code "166") (name "VIN") (class "Default")
      (node (ref "C1") (pin "1") (pinfunction "1_1") (pintype "passive"))
      (node (ref "C3") (pin "2") (pinfunction "2_2") (pintype "bidirectional"))
      (node (ref "C4") (pin "1") (pinfunction "1_1") (pintype "passive"))
      (node (ref "C8") (pin "2") (pinfunction "2_2") (pintype "bidirectional"))
      (node (ref "D2") (pin "A") (pinfunction "A_A") (pintype "passive"))
      (node (ref "DRV1") (pin "VMOT") (pinfunction "VMOT_VMOT") (pintype "bidirectional"))
      (node (ref "DRV2") (pin "VMOT") (pinfunction "VMOT_VMOT") (pintype "bidirectional"))
      (node (ref "F1") (pin "P$2") (pinfunction "2_P$2") (pintype "bidirectional"))
      (node (ref "IC2") (pin "3") (pinfunction "IN_3") (pintype "input"))
      (node (ref "IC3") (pin "3") (pinfunction "IN_3") (pintype "input"))
      (node (ref "J6") (pin "3") (pinfunction "3_3") (pintype "passive"))
      (node (ref "JP13") (pin "4") (pinfunction "4_4") (pintype "passive"))
      (node (ref "JP5") (pin "11") (pinfunction "11_11") (pintype "passive"))
      (node (ref "JP5") (pin "12") (pinfunction "12_12") (pintype "passive"))
      (node (ref "R1") (pin "1") (pinfunction "1_1") (pintype "passive"))
      (node (ref "R7") (pin "1") (pinfunction "1_1") (pintype "passive"))
      (node (ref "SJ1") (pin "2") (pinfunction "2_2") (pintype "passive"))
    )
    (net (code "167") (name "VIN*") (class "Default")
      (node (ref "J2") (pin "8") (pinfunction "8_8") (pintype "passive"))
      (node (ref "JP3") (pin "4") (pinfunction "4_4") (pintype "passive"))
    )
    (net (code "168") (name "VIN_") (class "Default")
      (node (ref "JP12") (pin "13") (pinfunction "13_13") (pintype "passive"))
    )
    (net (code "169") (name "VSELECT") (class "Default")
      (node (ref "DRV1") (pin "FLT") (pinfunction "FLT_FLT") (pintype "bidirectional"))
      (node (ref "DRV2") (pin "FLT") (pinfunction "FLT_FLT") (pintype "bidirectional"))
      (node (ref "IC1") (pin "1") (pinfunction "VCC(A)_1") (pintype "power_in"))
      (node (ref "IC1") (pin "5") (pinfunction "DIR_5") (pintype "input"))
      (node (ref "IC7") (pin "16") (pinfunction "VDD_16") (pintype "bidirectional"))
      (node (ref "JP15") (pin "2") (pinfunction "2_2") (pintype "passive"))
      (node (ref "R30") (pin "1") (pinfunction "1_1") (pintype "passive"))
      (node (ref "R31") (pin "1") (pinfunction "1_1") (pintype "passive"))
      (node (ref "R32") (pin "1") (pinfunction "1_1") (pintype "passive"))
      (node (ref "R33") (pin "1") (pinfunction "1_1") (pintype "passive"))
      (node (ref "U1") (pin "5") (pinfunction "VCC_5") (pintype "power_in"))
      (node (ref "U2") (pin "5") (pinfunction "VCC_5") (pintype "power_in"))
    )
    (net (code "170") (name "VSELECT_") (class "Default")
      (node (ref "JP14") (pin "2") (pinfunction "2_2") (pintype "passive"))
      (node (ref "JP19") (pin "3") (pinfunction "3_3") (pintype "passive"))
      (node (ref "JP23") (pin "3") (pinfunction "3_3") (pintype "passive"))
      (node (ref "U10") (pin "5") (pinfunction "VCC_5") (pintype "power_in"))
      (node (ref "U11") (pin "5") (pinfunction "VCC_5") (pintype "power_in"))
      (node (ref "U12") (pin "5") (pinfunction "VCC_5") (pintype "power_in"))
      (node (ref "U3") (pin "5") (pinfunction "VCC_5") (pintype "power_in"))
      (node (ref "U4") (pin "5") (pinfunction "VCC_5") (pintype "power_in"))
      (node (ref "U5") (pin "5") (pinfunction "VCC_5") (pintype "power_in"))
      (node (ref "U6") (pin "5") (pinfunction "VCC_5") (pintype "power_in"))
      (node (ref "U7") (pin "5") (pinfunction "VCC_5") (pintype "power_in"))
      (node (ref "U8") (pin "5") (pinfunction "VCC_5") (pintype "power_in"))
      (node (ref "U9") (pin "5") (pinfunction "VCC_5") (pintype "power_in"))
    )
    (net (code "171") (name "unconnected-(DRV1-(CONFIG)-PadCONFIG)") (class "Default")
      (node (ref "DRV1") (pin "CONFIG") (pinfunction "(CONFIG)_CONFIG") (pintype "bidirectional"))
    )
    (net (code "172") (name "unconnected-(DRV1-(VREF)-PadVREF)") (class "Default")
      (node (ref "DRV1") (pin "VREF") (pinfunction "(VREF)_VREF") (pintype "bidirectional"))
    )
    (net (code "173") (name "unconnected-(DRV1-PadSLP)") (class "Default")
      (node (ref "DRV1") (pin "SLP") (pinfunction "SLP_SLP") (pintype "bidirectional"))
    )
    (net (code "174") (name "unconnected-(DRV2-(CONFIG)-PadCONFIG)") (class "Default")
      (node (ref "DRV2") (pin "CONFIG") (pinfunction "(CONFIG)_CONFIG") (pintype "bidirectional"))
    )
    (net (code "175") (name "unconnected-(DRV2-(VREF)-PadVREF)") (class "Default")
      (node (ref "DRV2") (pin "VREF") (pinfunction "(VREF)_VREF") (pintype "bidirectional"))
    )
    (net (code "176") (name "unconnected-(DRV2-PadSLP)") (class "Default")
      (node (ref "DRV2") (pin "SLP") (pinfunction "SLP_SLP") (pintype "bidirectional"))
    )
    (net (code "177") (name "unconnected-(IC6-~{INT}-Pad13)") (class "Default")
      (node (ref "IC6") (pin "13") (pinfunction "~{INT}_13") (pintype "bidirectional"))
    )
    (net (code "178") (name "unconnected-(IC7-P3-Pad7)") (class "Default")
      (node (ref "IC7") (pin "7") (pinfunction "P3_7") (pintype "bidirectional"))
    )
    (net (code "179") (name "unconnected-(IC7-~{INT}-Pad13)") (class "Default")
      (node (ref "IC7") (pin "13") (pinfunction "~{INT}_13") (pintype "bidirectional"))
    )
    (net (code "180") (name "unconnected-(J2-Pad1)") (class "Default")
      (node (ref "J2") (pin "1") (pinfunction "1_1") (pintype "passive"))
    )
    (net (code "181") (name "unconnected-(J2-Pad2)") (class "Default")
      (node (ref "J2") (pin "2") (pinfunction "2_2") (pintype "passive"))
    )
    (net (code "182") (name "unconnected-(J2-Pad3)") (class "Default")
      (node (ref "J2") (pin "3") (pinfunction "3_3") (pintype "passive"))
    )
    (net (code "183") (name "unconnected-(J2-Pad4)") (class "Default")
      (node (ref "J2") (pin "4") (pinfunction "4_4") (pintype "passive"))
    )
    (net (code "184") (name "unconnected-(J2-Pad5)") (class "Default")
      (node (ref "J2") (pin "5") (pinfunction "5_5") (pintype "passive"))
    )
    (net (code "185") (name "unconnected-(J4-Pad8)") (class "Default")
      (node (ref "J4") (pin "8") (pinfunction "8_8") (pintype "passive"))
    )
    (net (code "186") (name "unconnected-(JP12-Pad12)") (class "Default")
      (node (ref "JP12") (pin "12") (pinfunction "12_12") (pintype "passive"))
    )
    (net (code "187") (name "unconnected-(JP13-Pad5)") (class "Default")
      (node (ref "JP13") (pin "5") (pinfunction "5_5") (pintype "passive"))
    )
    (net (code "188") (name "unconnected-(PLED9-DO-Pad1)") (class "Default")
      (node (ref "PLED9") (pin "1") (pinfunction "DO_1") (pintype "bidirectional"))
    )
    (net (code "189") (name "unconnected-(S1-Pad1)") (class "Default")
      (node (ref "S1") (pin "1") (pinfunction "1_1") (pintype "bidirectional"))
    )
    (net (code "190") (name "unconnected-(S2-Pad7)") (class "Default")
      (node (ref "S2") (pin "7") (pinfunction "7_7") (pintype "bidirectional"))
    )
    (net (code "191") (name "unconnected-(S2-Pad8)") (class "Default")
      (node (ref "S2") (pin "8") (pinfunction "8_8") (pintype "bidirectional"))
    )
  )
)
